# Power_supply.net
KiCad netlist of a schematic drawn in Altium Designer
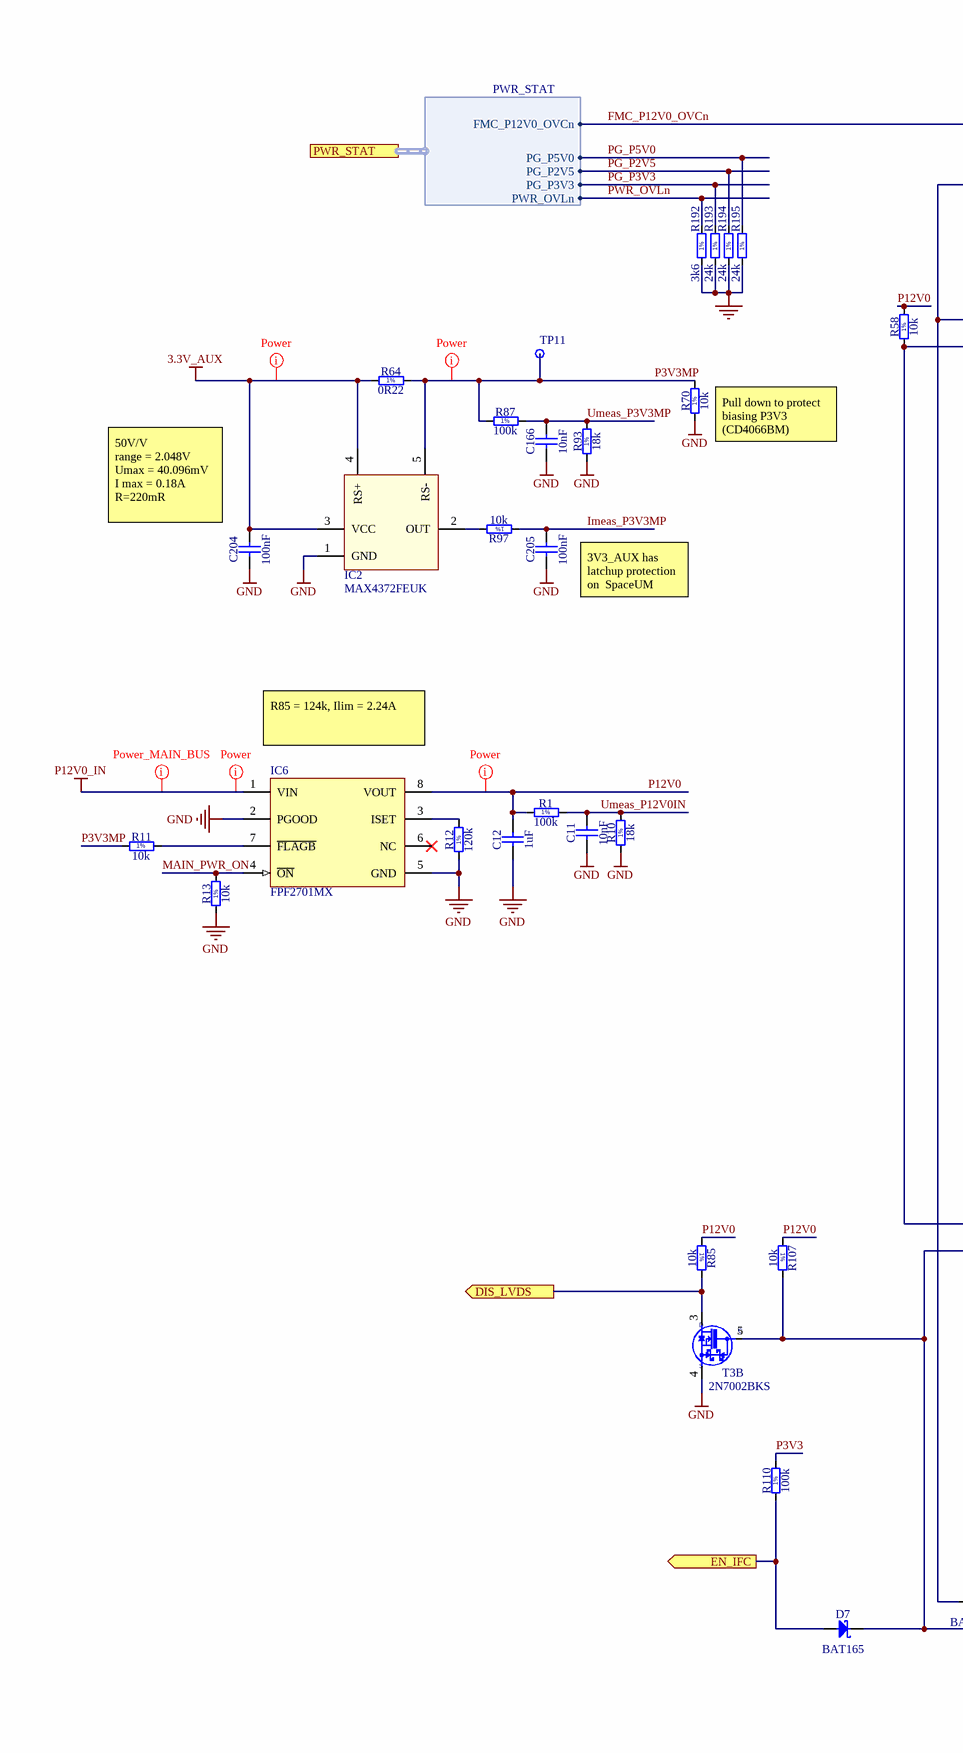
[diagram p0: Power_supply.SchDoc, left]
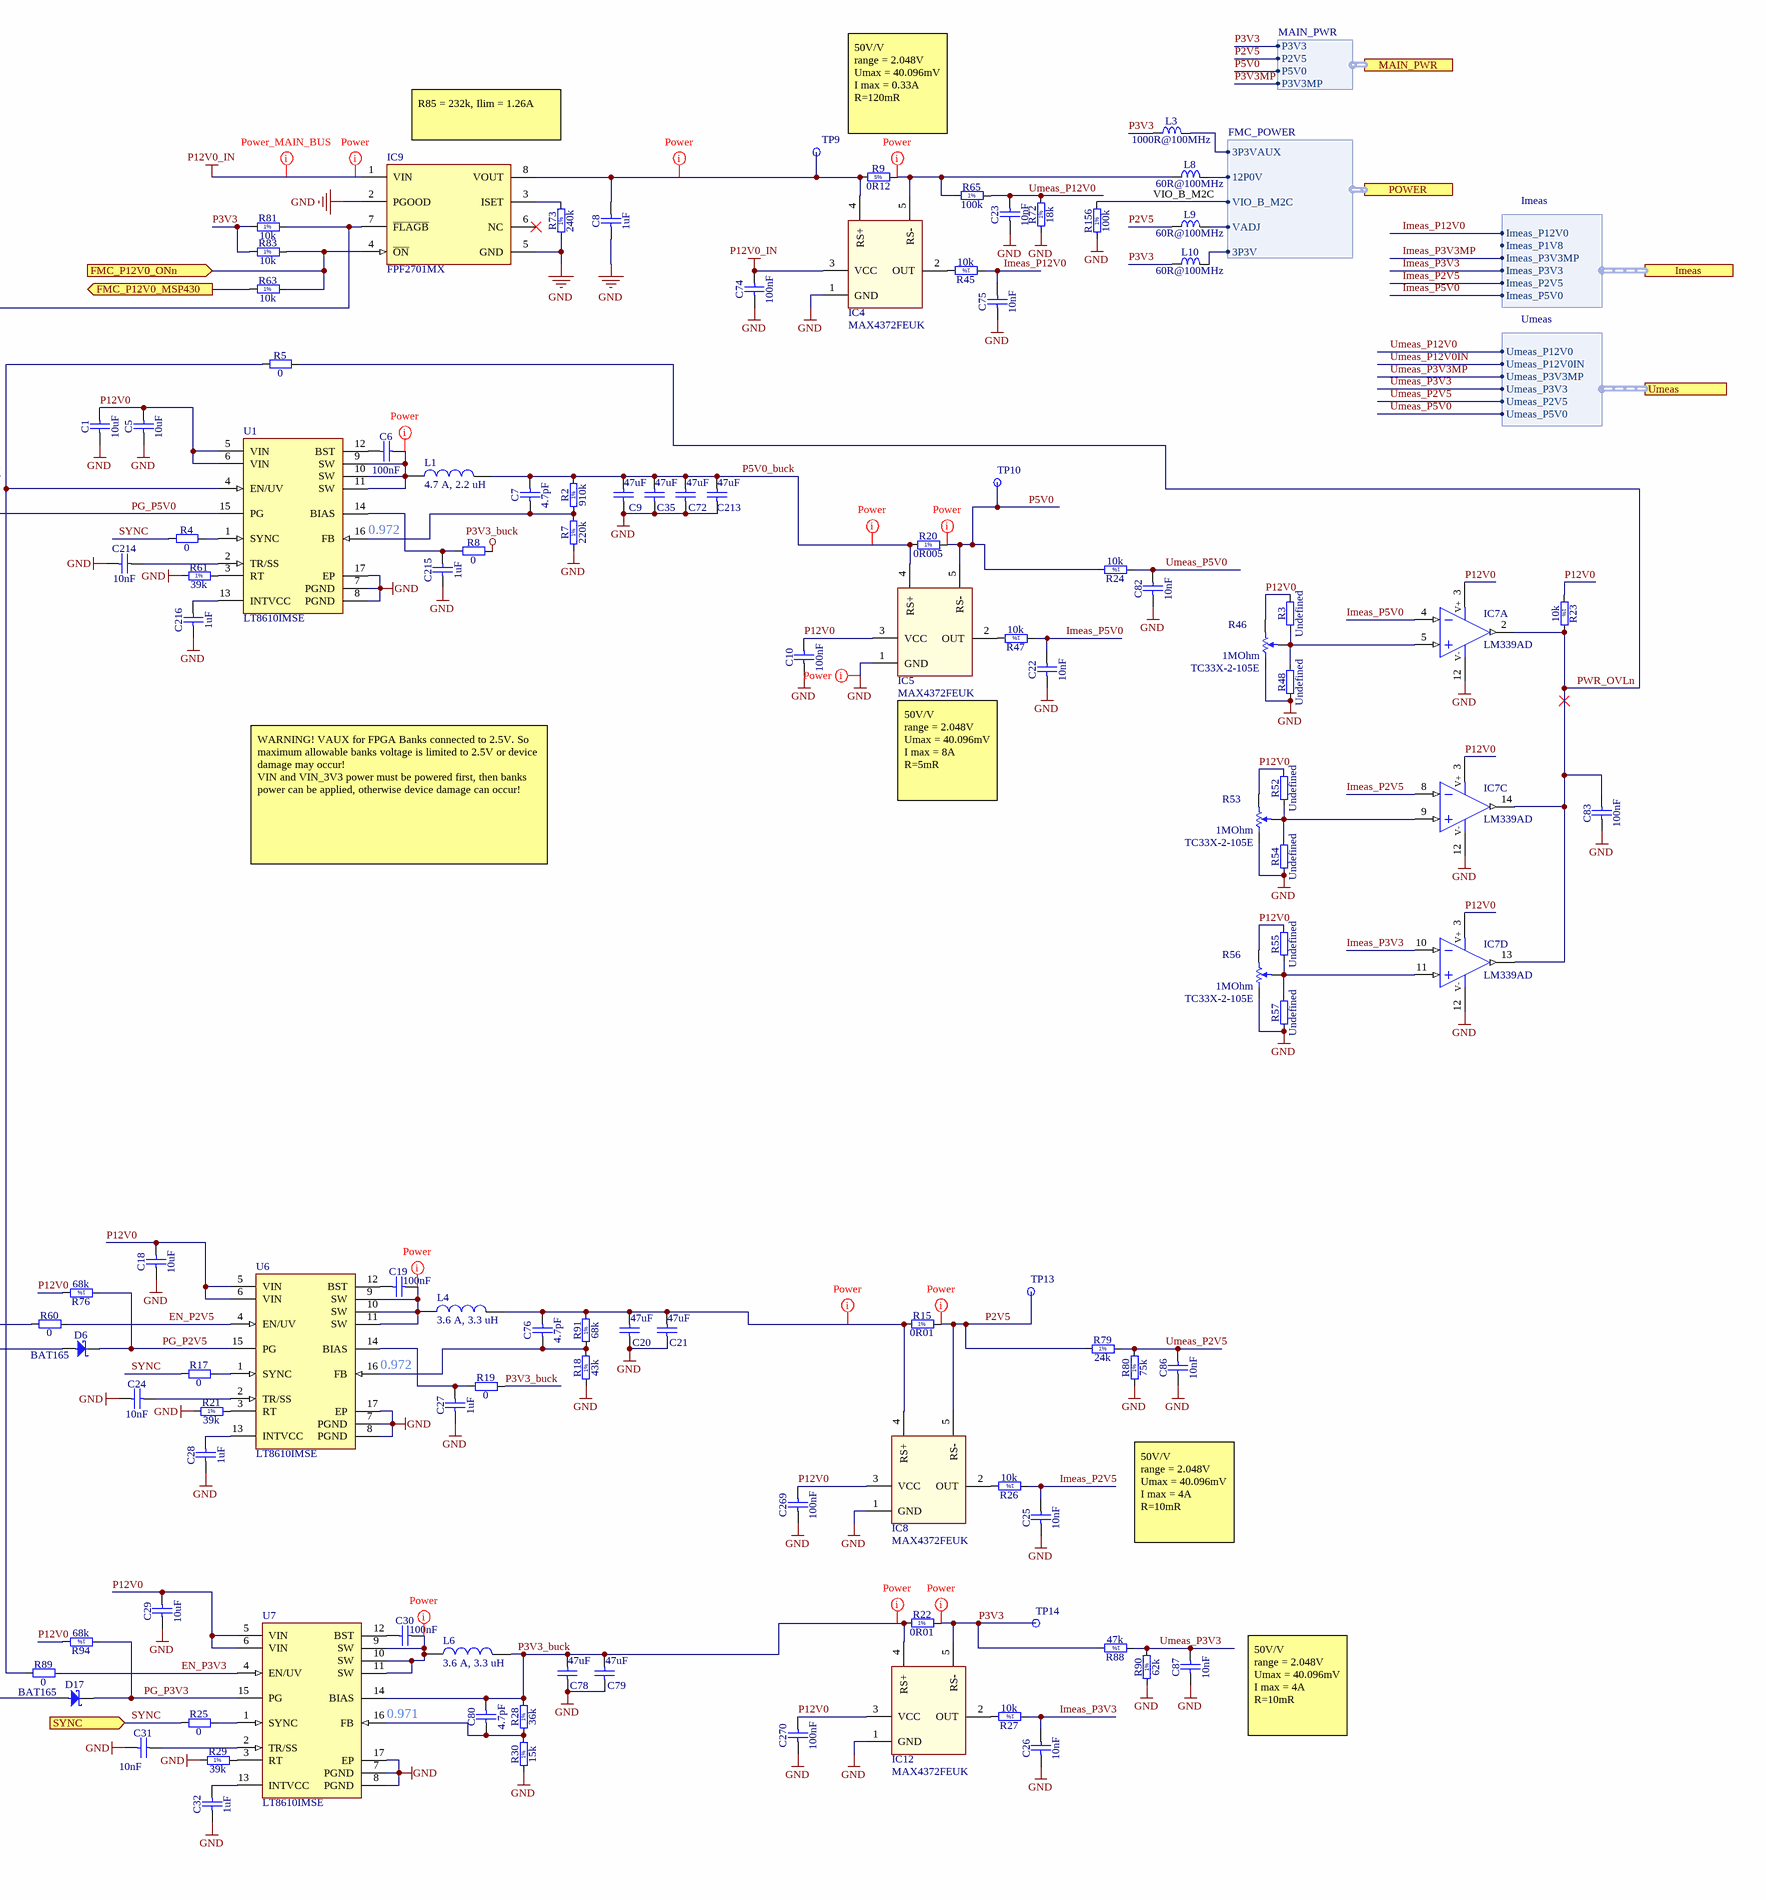
[diagram p1: Power_supply.SchDoc, right]

(export (version "E")
  (design (tool "Eeschema 10.0.6"))
  (components
    (comp (ref "C1")
      (value "10uF")
      (footprint "CAPC2012X95N")
      (description "Non-polarised capacitor")
      (fields
        (field (name "PART NUMBER") "CC0805_10UF_25V_10%_X5R")
        (field (name "VOLTAGE") "25V")
        (field (name "AUTHOR") "CERN DEM JLC")
      )
      (libsource (lib "Capacitors") (part "Capacitor - non polarized"))
    )
    (comp (ref "C5")
      (value "10uF")
      (footprint "CAPC2012X95N")
      (description "Non-polarised capacitor")
      (fields
        (field (name "PART NUMBER") "CC0805_10UF_25V_10%_X5R")
        (field (name "VOLTAGE") "25V")
        (field (name "AUTHOR") "CERN DEM JLC")
      )
      (libsource (lib "Capacitors") (part "Capacitor - non polarized"))
    )
    (comp (ref "C6")
      (value "100nF")
      (footprint "CAPC1005X55N")
      (description "Non-polarised capacitor")
      (fields
        (field (name "PART NUMBER") "CC0402_100NF_25V_10%_X7R_YUDEN_TMK105B7104KVHF")
        (field (name "VOLTAGE") "25V")
        (field (name "AUTHOR") "CERN DEM JLC")
      )
      (libsource (lib "Capacitors") (part "Capacitor - non polarized"))
    )
    (comp (ref "C7")
      (value "4.7pF")
      (footprint "CAPC1005X55N")
      (description "Non-polarised capacitor")
      (fields
        (field (name "PART NUMBER") "CC0402_4.7PF_50V_0.25PF_C0G")
        (field (name "VOLTAGE") "50V")
        (field (name "AUTHOR") "CERN DEM JLC")
      )
      (libsource (lib "Capacitors") (part "Capacitor - non polarized"))
    )
    (comp (ref "C8")
      (value "1uF")
      (footprint "CAPC1608X87N")
      (description "Non-polarised capacitor")
      (fields
        (field (name "PART NUMBER") "CC0603_1UF_25V_10%_X7R")
        (field (name "VOLTAGE") "25V")
        (field (name "AUTHOR") "CERN DEM JLC")
      )
      (libsource (lib "Capacitors") (part "Capacitor - non polarized"))
    )
    (comp (ref "C9")
      (value "47uF")
      (footprint "CAPC2012X140N")
      (description "Non-polarised capacitor")
      (fields
        (field (name "PART NUMBER") "CC0805_47UF_6.3V_20%_X5R")
        (field (name "MANUFACTURER") "GENERIC")
        (field (name "AUTHOR") "CERN DEM JLC")
      )
      (libsource (lib "Capacitors") (part "Capacitor - non polarized"))
    )
    (comp (ref "C10")
      (value "100nF")
      (footprint "CAPC1005X55N")
      (description "Non-polarised capacitor")
      (fields
        (field (name "PART NUMBER") "CC0402_100NF_25V_10%_X7R_YUDEN_TMK105B7104KVHF")
        (field (name "VOLTAGE") "25V")
        (field (name "AUTHOR") "CERN DEM JLC")
      )
      (libsource (lib "Capacitors") (part "Capacitor - non polarized"))
    )
    (comp (ref "C11")
      (value "10nF")
      (footprint "CAPC1005X55N")
      (description "Non-polarised capacitor")
      (fields
        (field (name "PART NUMBER") "CC0402_10NF_50V_10%_X7R")
        (field (name "VOLTAGE") "50V")
        (field (name "AUTHOR") "CERN DEM MR")
      )
      (libsource (lib "Capacitors") (part "Capacitor - non polarized"))
    )
    (comp (ref "C12")
      (value "1uF")
      (footprint "CAPC1608X87N")
      (description "Non-polarised capacitor")
      (fields
        (field (name "PART NUMBER") "CC0603_1UF_25V_10%_X7R")
        (field (name "VOLTAGE") "25V")
        (field (name "AUTHOR") "CERN DEM JLC")
      )
      (libsource (lib "Capacitors") (part "Capacitor - non polarized"))
    )
    (comp (ref "C18")
      (value "10uF")
      (footprint "CAPC2012X95N")
      (description "Non-polarised capacitor")
      (fields
        (field (name "PART NUMBER") "CC0805_10UF_25V_10%_X5R")
        (field (name "VOLTAGE") "25V")
        (field (name "AUTHOR") "CERN DEM JLC")
      )
      (libsource (lib "Capacitors") (part "Capacitor - non polarized"))
    )
    (comp (ref "C19")
      (value "100nF")
      (footprint "CAPC1005X55N")
      (description "Non-polarised capacitor")
      (fields
        (field (name "PART NUMBER") "CC0402_100NF_25V_10%_X7R_YUDEN_TMK105B7104KVHF")
        (field (name "VOLTAGE") "25V")
        (field (name "AUTHOR") "CERN DEM JLC")
      )
      (libsource (lib "Capacitors") (part "Capacitor - non polarized"))
    )
    (comp (ref "C20")
      (value "47uF")
      (footprint "CAPC2012X140N")
      (description "Non-polarised capacitor")
      (fields
        (field (name "PART NUMBER") "CC0805_47UF_6.3V_20%_X5R")
        (field (name "MANUFACTURER") "GENERIC")
        (field (name "AUTHOR") "CERN DEM JLC")
      )
      (libsource (lib "Capacitors") (part "Capacitor - non polarized"))
    )
    (comp (ref "C21")
      (value "47uF")
      (footprint "CAPC2012X140N")
      (description "Non-polarised capacitor")
      (fields
        (field (name "PART NUMBER") "CC0805_47UF_6.3V_20%_X5R")
        (field (name "MANUFACTURER") "GENERIC")
        (field (name "AUTHOR") "CERN DEM JLC")
      )
      (libsource (lib "Capacitors") (part "Capacitor - non polarized"))
    )
    (comp (ref "C22")
      (value "10nF")
      (footprint "CAPC1005X55N")
      (description "Non-polarised capacitor")
      (fields
        (field (name "PART NUMBER") "CC0402_10NF_50V_10%_X7R")
        (field (name "VOLTAGE") "50V")
        (field (name "AUTHOR") "CERN DEM MR")
      )
      (libsource (lib "Capacitors") (part "Capacitor - non polarized"))
    )
    (comp (ref "C23")
      (value "10nF")
      (footprint "CAPC1005X55N")
      (description "Non-polarised capacitor")
      (fields
        (field (name "PART NUMBER") "CC0402_10NF_50V_10%_X7R")
        (field (name "VOLTAGE") "50V")
        (field (name "AUTHOR") "CERN DEM MR")
      )
      (libsource (lib "Capacitors") (part "Capacitor - non polarized"))
    )
    (comp (ref "C24")
      (value "10nF")
      (footprint "CAPC1005X55N")
      (description "Non-polarised capacitor")
      (fields
        (field (name "PART NUMBER") "CC0402_10NF_25V_10%_X7R")
        (field (name "VOLTAGE") "25V")
        (field (name "AUTHOR") "CERN DEM JLC")
      )
      (libsource (lib "Capacitors") (part "Capacitor - non polarized"))
    )
    (comp (ref "C25")
      (value "10nF")
      (footprint "CAPC1005X55N")
      (description "Non-polarised capacitor")
      (fields
        (field (name "PART NUMBER") "CC0402_10NF_50V_10%_X7R")
        (field (name "VOLTAGE") "50V")
        (field (name "AUTHOR") "CERN DEM MR")
      )
      (libsource (lib "Capacitors") (part "Capacitor - non polarized"))
    )
    (comp (ref "C26")
      (value "10nF")
      (footprint "CAPC1005X55N")
      (description "Non-polarised capacitor")
      (fields
        (field (name "PART NUMBER") "CC0402_10NF_50V_10%_X7R")
        (field (name "VOLTAGE") "50V")
        (field (name "AUTHOR") "CERN DEM MR")
      )
      (libsource (lib "Capacitors") (part "Capacitor - non polarized"))
    )
    (comp (ref "C27")
      (value "1uF")
      (footprint "CAPC1608X87N")
      (description "Non-polarised capacitor")
      (fields
        (field (name "PART NUMBER") "CC0603_1UF_25V_10%_X7R")
        (field (name "VOLTAGE") "25V")
        (field (name "AUTHOR") "CERN DEM JLC")
      )
      (libsource (lib "Capacitors") (part "Capacitor - non polarized"))
    )
    (comp (ref "C28")
      (value "1uF")
      (footprint "CAPC1608X87N")
      (description "Non-polarised capacitor")
      (fields
        (field (name "PART NUMBER") "CC0603_1UF_25V_10%_X7R")
        (field (name "VOLTAGE") "25V")
        (field (name "AUTHOR") "CERN DEM JLC")
      )
      (libsource (lib "Capacitors") (part "Capacitor - non polarized"))
    )
    (comp (ref "C29")
      (value "10uF")
      (footprint "CAPC2012X95N")
      (description "Non-polarised capacitor")
      (fields
        (field (name "PART NUMBER") "CC0805_10UF_25V_10%_X5R")
        (field (name "VOLTAGE") "25V")
        (field (name "AUTHOR") "CERN DEM JLC")
      )
      (libsource (lib "Capacitors") (part "Capacitor - non polarized"))
    )
    (comp (ref "C30")
      (value "100nF")
      (footprint "CAPC1005X55N")
      (description "Non-polarised capacitor")
      (fields
        (field (name "PART NUMBER") "CC0402_100NF_25V_10%_X7R_YUDEN_TMK105B7104KVHF")
        (field (name "VOLTAGE") "25V")
        (field (name "AUTHOR") "CERN DEM JLC")
      )
      (libsource (lib "Capacitors") (part "Capacitor - non polarized"))
    )
    (comp (ref "C31")
      (value "10nF")
      (footprint "CAPC1005X55N")
      (description "Non-polarised capacitor")
      (fields
        (field (name "PART NUMBER") "CC0402_10NF_25V_10%_X7R")
        (field (name "VOLTAGE") "25V")
        (field (name "AUTHOR") "CERN DEM JLC")
      )
      (libsource (lib "Capacitors") (part "Capacitor - non polarized"))
    )
    (comp (ref "C32")
      (value "1uF")
      (footprint "CAPC1608X87N")
      (description "Non-polarised capacitor")
      (fields
        (field (name "PART NUMBER") "CC0603_1UF_25V_10%_X7R")
        (field (name "VOLTAGE") "25V")
        (field (name "AUTHOR") "CERN DEM JLC")
      )
      (libsource (lib "Capacitors") (part "Capacitor - non polarized"))
    )
    (comp (ref "C35")
      (value "47uF")
      (footprint "CAPC2012X140N")
      (description "Non-polarised capacitor")
      (fields
        (field (name "PART NUMBER") "CC0805_47UF_6.3V_20%_X5R")
        (field (name "MANUFACTURER") "GENERIC")
        (field (name "AUTHOR") "CERN DEM JLC")
      )
      (libsource (lib "Capacitors") (part "Capacitor - non polarized"))
    )
    (comp (ref "C72")
      (value "47uF")
      (footprint "CAPC2012X140N")
      (description "Non-polarised capacitor")
      (fields
        (field (name "PART NUMBER") "CC0805_47UF_6.3V_20%_X5R")
        (field (name "MANUFACTURER") "GENERIC")
        (field (name "AUTHOR") "CERN DEM JLC")
      )
      (libsource (lib "Capacitors") (part "Capacitor - non polarized"))
    )
    (comp (ref "C74")
      (value "100nF")
      (footprint "CAPC1005X55N")
      (description "Non-polarised capacitor")
      (fields
        (field (name "PART NUMBER") "CC0402_100NF_25V_10%_X7R_YUDEN_TMK105B7104KVHF")
        (field (name "VOLTAGE") "25V")
        (field (name "AUTHOR") "CERN DEM JLC")
      )
      (libsource (lib "Capacitors") (part "Capacitor - non polarized"))
    )
    (comp (ref "C75")
      (value "10nF")
      (footprint "CAPC1005X55N")
      (description "Non-polarised capacitor")
      (fields
        (field (name "PART NUMBER") "CC0402_10NF_50V_10%_X7R")
        (field (name "VOLTAGE") "50V")
        (field (name "AUTHOR") "CERN DEM MR")
      )
      (libsource (lib "Capacitors") (part "Capacitor - non polarized"))
    )
    (comp (ref "C76")
      (value "4.7pF")
      (footprint "CAPC1005X55N")
      (description "Non-polarised capacitor")
      (fields
        (field (name "PART NUMBER") "CC0402_4.7PF_50V_0.25PF_C0G")
        (field (name "VOLTAGE") "50V")
        (field (name "AUTHOR") "CERN DEM JLC")
      )
      (libsource (lib "Capacitors") (part "Capacitor - non polarized"))
    )
    (comp (ref "C78")
      (value "47uF")
      (footprint "CAPC2012X140N")
      (description "Non-polarised capacitor")
      (fields
        (field (name "PART NUMBER") "CC0805_47UF_6.3V_20%_X5R")
        (field (name "MANUFACTURER") "GENERIC")
        (field (name "AUTHOR") "CERN DEM JLC")
      )
      (libsource (lib "Capacitors") (part "Capacitor - non polarized"))
    )
    (comp (ref "C79")
      (value "47uF")
      (footprint "CAPC2012X140N")
      (description "Non-polarised capacitor")
      (fields
        (field (name "PART NUMBER") "CC0805_47UF_6.3V_20%_X5R")
        (field (name "MANUFACTURER") "GENERIC")
        (field (name "AUTHOR") "CERN DEM JLC")
      )
      (libsource (lib "Capacitors") (part "Capacitor - non polarized"))
    )
    (comp (ref "C80")
      (value "4.7pF")
      (footprint "CAPC1005X55N")
      (description "Non-polarised capacitor")
      (fields
        (field (name "PART NUMBER") "CC0402_4.7PF_50V_0.25PF_C0G")
        (field (name "VOLTAGE") "50V")
        (field (name "AUTHOR") "CERN DEM JLC")
      )
      (libsource (lib "Capacitors") (part "Capacitor - non polarized"))
    )
    (comp (ref "C82")
      (value "10nF")
      (footprint "CAPC1005X55N")
      (description "Non-polarised capacitor")
      (fields
        (field (name "PART NUMBER") "CC0402_10NF_50V_10%_X7R")
        (field (name "VOLTAGE") "50V")
        (field (name "AUTHOR") "CERN DEM MR")
      )
      (libsource (lib "Capacitors") (part "Capacitor - non polarized"))
    )
    (comp (ref "C83")
      (value "100nF")
      (footprint "CAPC1005X55N")
      (description "Non-polarised capacitor")
      (fields
        (field (name "PART NUMBER") "CC0402_100NF_25V_10%_X7R_YUDEN_TMK105B7104KVHF")
        (field (name "VOLTAGE") "25V")
        (field (name "AUTHOR") "CERN DEM JLC")
      )
      (libsource (lib "Capacitors") (part "Capacitor - non polarized"))
    )
    (comp (ref "C86")
      (value "10nF")
      (footprint "CAPC1005X55N")
      (description "Non-polarised capacitor")
      (fields
        (field (name "PART NUMBER") "CC0402_10NF_50V_10%_X7R")
        (field (name "VOLTAGE") "50V")
        (field (name "AUTHOR") "CERN DEM MR")
      )
      (libsource (lib "Capacitors") (part "Capacitor - non polarized"))
    )
    (comp (ref "C87")
      (value "10nF")
      (footprint "CAPC1005X55N")
      (description "Non-polarised capacitor")
      (fields
        (field (name "PART NUMBER") "CC0402_10NF_50V_10%_X7R")
        (field (name "VOLTAGE") "50V")
        (field (name "AUTHOR") "CERN DEM MR")
      )
      (libsource (lib "Capacitors") (part "Capacitor - non polarized"))
    )
    (comp (ref "C166")
      (value "10nF")
      (footprint "CAPC1005X55N")
      (description "Non-polarised capacitor")
      (fields
        (field (name "PART NUMBER") "CC0402_10NF_50V_10%_X7R")
        (field (name "VOLTAGE") "50V")
        (field (name "AUTHOR") "CERN DEM MR")
      )
      (libsource (lib "Capacitors") (part "Capacitor - non polarized"))
    )
    (comp (ref "C204")
      (value "100nF")
      (footprint "CAPC1005X55N")
      (description "Non-polarised capacitor")
      (fields
        (field (name "PART NUMBER") "CC0402_100NF_25V_10%_X7R_YUDEN_TMK105B7104KVHF")
        (field (name "VOLTAGE") "25V")
        (field (name "AUTHOR") "CERN DEM JLC")
      )
      (libsource (lib "Capacitors") (part "Capacitor - non polarized"))
    )
    (comp (ref "C205")
      (value "100nF")
      (footprint "CAPC1005X55N")
      (description "Non-polarised capacitor")
      (fields
        (field (name "PART NUMBER") "CC0402_100NF_25V_10%_X7R_YUDEN_TMK105B7104KVHF")
        (field (name "VOLTAGE") "25V")
        (field (name "AUTHOR") "CERN DEM JLC")
      )
      (libsource (lib "Capacitors") (part "Capacitor - non polarized"))
    )
    (comp (ref "C213")
      (value "47uF")
      (footprint "CAPC2012X140N")
      (description "Non-polarised capacitor")
      (fields
        (field (name "PART NUMBER") "CC0805_47UF_6.3V_20%_X5R")
        (field (name "MANUFACTURER") "GENERIC")
        (field (name "AUTHOR") "CERN DEM JLC")
      )
      (libsource (lib "Capacitors") (part "Capacitor - non polarized"))
    )
    (comp (ref "C214")
      (value "10nF")
      (footprint "CAPC1005X55N")
      (description "Non-polarised capacitor")
      (fields
        (field (name "PART NUMBER") "CC0402_10NF_25V_10%_X7R")
        (field (name "VOLTAGE") "25V")
        (field (name "AUTHOR") "CERN DEM JLC")
      )
      (libsource (lib "Capacitors") (part "Capacitor - non polarized"))
    )
    (comp (ref "C215")
      (value "1uF")
      (footprint "CAPC1608X87N")
      (description "Non-polarised capacitor")
      (fields
        (field (name "PART NUMBER") "CC0603_1UF_25V_10%_X7R")
        (field (name "VOLTAGE") "25V")
        (field (name "AUTHOR") "CERN DEM JLC")
      )
      (libsource (lib "Capacitors") (part "Capacitor - non polarized"))
    )
    (comp (ref "C216")
      (value "1uF")
      (footprint "CAPC1608X87N")
      (description "Non-polarised capacitor")
      (fields
        (field (name "PART NUMBER") "CC0603_1UF_25V_10%_X7R")
        (field (name "VOLTAGE") "25V")
        (field (name "AUTHOR") "CERN DEM JLC")
      )
      (libsource (lib "Capacitors") (part "Capacitor - non polarized"))
    )
    (comp (ref "C269")
      (value "100nF")
      (footprint "CAPC1005X55N")
      (description "Non-polarised capacitor")
      (fields
        (field (name "PART NUMBER") "CC0402_100NF_25V_10%_X7R_YUDEN_TMK105B7104KVHF")
        (field (name "VOLTAGE") "25V")
        (field (name "AUTHOR") "CERN DEM JLC")
      )
      (libsource (lib "Capacitors") (part "Capacitor - non polarized"))
    )
    (comp (ref "C270")
      (value "100nF")
      (footprint "CAPC1005X55N")
      (description "Non-polarised capacitor")
      (fields
        (field (name "PART NUMBER") "CC0402_100NF_25V_10%_X7R_YUDEN_TMK105B7104KVHF")
        (field (name "VOLTAGE") "25V")
        (field (name "AUTHOR") "CERN DEM JLC")
      )
      (libsource (lib "Capacitors") (part "Capacitor - non polarized"))
    )
    (comp (ref "D6")
      (value "BAT165")
      (footprint "SOD2512X110N")
      (description "Schottky Diode")
      (fields
        (field (name "VOLTAGE") "40V")
        (field (name "POWER") "750mA")
        (field (name "AUTHOR") "CERN DEM JLC")
      )
      (libsource (lib "ICs And Semiconductors") (part "Diode Schottky"))
    )
    (comp (ref "D7")
      (value "BAT165")
      (footprint "SOD2512X110N")
      (description "Schottky Diode")
      (fields
        (field (name "VOLTAGE") "40V")
        (field (name "POWER") "750mA")
        (field (name "AUTHOR") "CERN DEM JLC")
      )
      (libsource (lib "ICs And Semiconductors") (part "Diode Schottky"))
    )
    (comp (ref "D17")
      (value "BAT165")
      (footprint "SOD2512X110N")
      (description "Schottky Diode")
      (fields
        (field (name "VOLTAGE") "40V")
        (field (name "POWER") "750mA")
        (field (name "AUTHOR") "CERN DEM JLC")
      )
      (libsource (lib "ICs And Semiconductors") (part "Diode Schottky"))
    )
    (comp (ref "IC2")
      (value "MAX4372FEUK")
      (footprint "SOT95P270X145-5N")
      (description "High side current sense amplifier (x50)")
      (fields (field (name "MANUFACTURER") "Maxim"))
      (libsource (lib "ICs_And_Semiconductors") (part "MAX4372FEUK"))
    )
    (comp (ref "IC4")
      (value "MAX4372FEUK")
      (footprint "SOT95P270X145-5N")
      (fields (field (name "MANUFACTURER") "Maxim"))
      (libsource (lib "LIBRARY_SCH") (part "PM_MAX4372FEUK"))
    )
    (comp (ref "IC5")
      (value "MAX4372FEUK")
      (footprint "SOT95P270X145-5N")
      (fields (field (name "MANUFACTURER") "Maxim"))
      (libsource (lib "LIBRARY_SCH") (part "PM_MAX4372FEUK"))
    )
    (comp (ref "IC6")
      (value "FPF2701MX")
      (footprint "SOIC127P600X175-8N")
      (description "Adjustable Over-current Protection Load Switch")
      (fields (field (name "MANUFACTURER") "ON Semiconductor"))
      (libsource (lib "ICs_And_Semiconductors") (part "FPF2701MX"))
    )
    (comp (ref "IC7")
      (value "LM339AD")
      (footprint "SOIC127P600X175-14N")
      (description "Quad Operational Amplifier")
      (fields (field (name "MANUFACTURER") "TEXAS INSTRUMENTS") (field (name "AUTHOR") "CERN DEM JLC"))
      (libsource (lib "ICs And Semiconductors") (part "Operational Amplifier x4 Type2"))
    )
    (comp (ref "IC8")
      (value "MAX4372FEUK")
      (footprint "SOT95P270X145-5N")
      (fields (field (name "MANUFACTURER") "Maxim"))
      (libsource (lib "LIBRARY_SCH") (part "PM_MAX4372FEUK"))
    )
    (comp (ref "IC9")
      (value "FPF2701MX")
      (footprint "SOIC127P600X175-8N")
      (description "Adjustable Over-current Protection Load Switch")
      (fields (field (name "MANUFACTURER") "ON Semiconductor"))
      (libsource (lib "ICs_And_Semiconductors") (part "FPF2701MX"))
    )
    (comp (ref "IC12")
      (value "MAX4372FEUK")
      (footprint "SOT95P270X145-5N")
      (fields (field (name "MANUFACTURER") "Maxim"))
      (libsource (lib "LIBRARY_SCH") (part "PM_MAX4372FEUK"))
    )
    (comp (ref "L1")
      (value "4.7 A, 2.2 uH")
      (footprint "WE-MAIA_4020")
      (description "WE-MAIA SMD Power Inductor, size 4020, 4.7 A, 2.2 uH")
      (fields (field (name "PART NUMBER") "78438356022") (field (name "PUBLISHER") "Wurth Elektronik"))
      (libsource (lib "ALTIUM-WE-MAIA-rev17b") (part "78438356022"))
    )
    (comp (ref "L3")
      (value "1000R@100MHz")
      (footprint "INDC1608X95N")
      (description "Inductor")
      (fields
        (field (name "PART NUMBER") "IND0603_MURATA_BLM18HE102SN1")
        (field (name "POWER") "600mA")
        (field (name "AUTHOR") "CERN DEM JLC")
      )
      (libsource (lib "Inductors & Transformers") (part "Inductor"))
    )
    (comp (ref "L4")
      (value "3.6 A, 3.3 uH")
      (footprint "WE-MAIA_4020")
      (description "WE-MAIA SMD Power Inductor, size 4020, 3.6 A, 3.3 uH")
      (fields (field (name "PART NUMBER") "78438356033") (field (name "PUBLISHER") "Wurth Elektronik"))
      (libsource (lib "ALTIUM-WE-MAIA-rev17b") (part "78438356033"))
    )
    (comp (ref "L6")
      (value "3.6 A, 3.3 uH")
      (footprint "WE-MAIA_4020")
      (description "WE-MAIA SMD Power Inductor, size 4020, 3.6 A, 3.3 uH")
      (fields (field (name "PART NUMBER") "78438356033") (field (name "PUBLISHER") "Wurth Elektronik"))
      (libsource (lib "ALTIUM-WE-MAIA-rev17b") (part "78438356033"))
    )
    (comp (ref "L8")
      (value "60R@100MHz")
      (footprint "INDC4516X180N")
      (description "Inductor")
      (fields
        (field (name "PART NUMBER") "IND1806_MURATA_BLM41PG600SN1L")
        (field (name "POWER") "6A")
        (field (name "AUTHOR") "CERN DEM JLC")
      )
      (libsource (lib "Inductors & Transformers") (part "Inductor"))
    )
    (comp (ref "L9")
      (value "60R@100MHz")
      (footprint "INDC4516X180N")
      (description "Inductor")
      (fields
        (field (name "PART NUMBER") "IND1806_MURATA_BLM41PG600SN1L")
        (field (name "POWER") "6A")
        (field (name "AUTHOR") "CERN DEM JLC")
      )
      (libsource (lib "Inductors & Transformers") (part "Inductor"))
    )
    (comp (ref "L10")
      (value "60R@100MHz")
      (footprint "INDC4516X180N")
      (description "Inductor")
      (fields
        (field (name "PART NUMBER") "IND1806_MURATA_BLM41PG600SN1L")
        (field (name "POWER") "6A")
        (field (name "AUTHOR") "CERN DEM JLC")
      )
      (libsource (lib "Inductors & Transformers") (part "Inductor"))
    )
    (comp (ref "R1")
      (value "100k")
      (footprint "RESC1005X40N")
      (description "Resistor - 1%")
      (fields
        (field (name "PART NUMBER") "R0402_100K_1%_0.0625W_100PPM")
        (field (name "POWER") "0.0625W")
        (field (name "AUTHOR") "CERN DEM JLC")
      )
      (libsource (lib "Resistors") (part "Resistor - 1%"))
    )
    (comp (ref "R2")
      (value "910k")
      (footprint "RESC1005X40N")
      (description "Resistor - 1%")
      (fields
        (field (name "PART NUMBER") "R0402_910K_1%_0.0625W_100PPM")
        (field (name "POWER") "0.0625W")
        (field (name "AUTHOR") "CERN DEM JLC")
      )
      (libsource (lib "Resistors") (part "Resistor - 1%"))
    )
    (comp (ref "R3")
      (value "Undefined")
      (footprint "RESC1005X40N")
      (description "Resistor")
      (fields (field (name "PART NUMBER") "R0402_NO-VALUE") (field (name "AUTHOR") "CERN DEM JLC"))
      (libsource (lib "Resistors") (part "Resistor"))
    )
    (comp (ref "R4")
      (value "0")
      (footprint "RESC1005X40N")
      (description "Resistor")
      (fields
        (field (name "PART NUMBER") "R0402_0R_JUMPER")
        (field (name "MANUFACTURER") "GENERIC")
        (field (name "AUTHOR") "CERN DEM JLC")
      )
      (libsource (lib "Resistors") (part "Resistor"))
    )
    (comp (ref "R5")
      (value "0")
      (footprint "RESC1005X40N")
      (description "Resistor")
      (fields
        (field (name "PART NUMBER") "R0402_0R_JUMPER")
        (field (name "MANUFACTURER") "GENERIC")
        (field (name "AUTHOR") "CERN DEM JLC")
      )
      (libsource (lib "Resistors") (part "Resistor"))
    )
    (comp (ref "R7")
      (value "220k")
      (footprint "RESC1005X40N")
      (description "Resistor - 1%")
      (fields
        (field (name "PART NUMBER") "R0402_220K_1%_0.0625W_100PPM")
        (field (name "POWER") "0.0625W")
        (field (name "AUTHOR") "CERN DEM JLC")
      )
      (libsource (lib "Resistors") (part "Resistor - 1%"))
    )
    (comp (ref "R8")
      (value "0")
      (footprint "RESC1005X40N")
      (description "Resistor")
      (fields
        (field (name "PART NUMBER") "R0402_0R_JUMPER")
        (field (name "MANUFACTURER") "GENERIC")
        (field (name "AUTHOR") "CERN DEM JLC")
      )
      (libsource (lib "Resistors") (part "Resistor"))
    )
    (comp (ref "R9")
      (value "0R12")
      (footprint "RESC2012X70N")
      (description "Resistor - 5%")
      (fields
        (field (name "PART NUMBER") "R0805_0R12_5%_0.25W_250PPM_PANASONIC_ERJ")
        (field (name "POWER") "0.25W")
        (field (name "AUTHOR") "CERN DEM JLC")
      )
      (libsource (lib "Resistors") (part "Resistor - 5%"))
    )
    (comp (ref "R10")
      (value "18k")
      (footprint "RESC1005X40N")
      (description "Resistor - 1%")
      (fields
        (field (name "PART NUMBER") "R0402_18K_1%_0.0625W_100PPM")
        (field (name "POWER") "0.0625W")
        (field (name "AUTHOR") "CERN DEM JLC")
      )
      (libsource (lib "Resistors") (part "Resistor - 1%"))
    )
    (comp (ref "R11")
      (value "10k")
      (footprint "RESC1005X40N")
      (description "Resistor - 1%")
      (fields
        (field (name "PART NUMBER") "R0402_10K_1%_0.0625W_100PPM")
        (field (name "POWER") "0.0625W")
        (field (name "AUTHOR") "CERN DEM JLC")
      )
      (libsource (lib "Resistors") (part "Resistor - 1%"))
    )
    (comp (ref "R12")
      (value "120k")
      (footprint "RESC1005X40N")
      (description "Resistor - 1%")
      (fields
        (field (name "PART NUMBER") "R0402_120K_1%_0.0625W_100PPM")
        (field (name "POWER") "0.0625W")
        (field (name "AUTHOR") "CERN DEM JLC")
      )
      (libsource (lib "Resistors") (part "Resistor - 1%"))
    )
    (comp (ref "R13")
      (value "10k")
      (footprint "RESC1005X40N")
      (description "Resistor - 1%")
      (fields
        (field (name "PART NUMBER") "R0402_10K_1%_0.0625W_100PPM")
        (field (name "POWER") "0.0625W")
        (field (name "AUTHOR") "CERN DEM JLC")
      )
      (libsource (lib "Resistors") (part "Resistor - 1%"))
    )
    (comp (ref "R15")
      (value "0R01")
      (footprint "RESC3216X80N")
      (description "Resistor - 1%")
      (fields
        (field (name "PART NUMBER") "R1206_0R01_1%_1W_100PPM_TT_LRMAM1206")
        (field (name "POWER") "1W")
        (field (name "AUTHOR") "CERN DEM BC")
      )
      (libsource (lib "Resistors") (part "Resistor - 1%"))
    )
    (comp (ref "R17")
      (value "0")
      (footprint "RESC1005X40N")
      (description "Resistor")
      (fields
        (field (name "PART NUMBER") "R0402_0R_JUMPER")
        (field (name "MANUFACTURER") "GENERIC")
        (field (name "AUTHOR") "CERN DEM JLC")
      )
      (libsource (lib "Resistors") (part "Resistor"))
    )
    (comp (ref "R18")
      (value "43k")
      (footprint "RESC1005X40N")
      (description "Resistor - 1%")
      (fields
        (field (name "PART NUMBER") "R0402_43K_1%_0.0625W_100PPM")
        (field (name "POWER") "0.0625W")
        (field (name "AUTHOR") "CERN DEM JLC")
      )
      (libsource (lib "Resistors") (part "Resistor - 1%"))
    )
    (comp (ref "R19")
      (value "0")
      (footprint "RESC1005X40N")
      (description "Resistor")
      (fields
        (field (name "PART NUMBER") "R0402_0R_JUMPER")
        (field (name "MANUFACTURER") "GENERIC")
        (field (name "AUTHOR") "CERN DEM JLC")
      )
      (libsource (lib "Resistors") (part "Resistor"))
    )
    (comp (ref "R20")
      (value "0R005")
      (footprint "RESC3216X80N")
      (description "Resistor - 1%")
      (fields
        (field (name "PART NUMBER") "R1206_0R005_1%_1W_100PPM_TT_LRMAM1206")
        (field (name "POWER") "1W")
        (field (name "AUTHOR") "CERN DEM BC")
      )
      (libsource (lib "Resistors") (part "Resistor - 1%"))
    )
    (comp (ref "R21")
      (value "39k")
      (footprint "RESC1005X40N")
      (description "Resistor - 1%")
      (fields
        (field (name "PART NUMBER") "R0402_39K_1%_0.0625W_100PPM")
        (field (name "POWER") "0.0625W")
        (field (name "AUTHOR") "CERN DEM JLC")
      )
      (libsource (lib "Resistors") (part "Resistor - 1%"))
    )
    (comp (ref "R22")
      (value "0R01")
      (footprint "RESC3216X80N")
      (description "Resistor - 1%")
      (fields
        (field (name "PART NUMBER") "R1206_0R01_1%_1W_100PPM_TT_LRMAM1206")
        (field (name "POWER") "1W")
        (field (name "AUTHOR") "CERN DEM BC")
      )
      (libsource (lib "Resistors") (part "Resistor - 1%"))
    )
    (comp (ref "R23")
      (value "10k")
      (footprint "RESC1005X40N")
      (description "Resistor - 1%")
      (fields
        (field (name "PART NUMBER") "R0402_10K_1%_0.0625W_100PPM")
        (field (name "POWER") "0.0625W")
        (field (name "AUTHOR") "CERN DEM JLC")
      )
      (libsource (lib "Resistors") (part "Resistor - 1%"))
    )
    (comp (ref "R24")
      (value "10k")
      (footprint "RESC1005X40N")
      (description "Resistor - 1%")
      (fields
        (field (name "PART NUMBER") "R0402_10K_1%_0.0625W_100PPM")
        (field (name "POWER") "0.0625W")
        (field (name "AUTHOR") "CERN DEM JLC")
      )
      (libsource (lib "Resistors") (part "Resistor - 1%"))
    )
    (comp (ref "R25")
      (value "0")
      (footprint "RESC1005X40N")
      (description "Resistor")
      (fields
        (field (name "PART NUMBER") "R0402_0R_JUMPER")
        (field (name "MANUFACTURER") "GENERIC")
        (field (name "AUTHOR") "CERN DEM JLC")
      )
      (libsource (lib "Resistors") (part "Resistor"))
    )
    (comp (ref "R26")
      (value "10k")
      (footprint "RESC1005X40N")
      (description "Resistor - 1%")
      (fields
        (field (name "PART NUMBER") "R0402_10K_1%_0.0625W_100PPM")
        (field (name "POWER") "0.0625W")
        (field (name "AUTHOR") "CERN DEM JLC")
      )
      (libsource (lib "Resistors") (part "Resistor - 1%"))
    )
    (comp (ref "R27")
      (value "10k")
      (footprint "RESC1005X40N")
      (description "Resistor - 1%")
      (fields
        (field (name "PART NUMBER") "R0402_10K_1%_0.0625W_100PPM")
        (field (name "POWER") "0.0625W")
        (field (name "AUTHOR") "CERN DEM JLC")
      )
      (libsource (lib "Resistors") (part "Resistor - 1%"))
    )
    (comp (ref "R28")
      (value "36k")
      (footprint "RESC1005X40N")
      (description "Resistor - 1%")
      (fields
        (field (name "PART NUMBER") "R0402_36K_1%_0.0625W_100PPM")
        (field (name "POWER") "0.0625W")
        (field (name "AUTHOR") "CERN DEM JLC")
      )
      (libsource (lib "Resistors") (part "Resistor - 1%"))
    )
    (comp (ref "R29")
      (value "39k")
      (footprint "RESC1005X40N")
      (description "Resistor - 1%")
      (fields
        (field (name "PART NUMBER") "R0402_39K_1%_0.0625W_100PPM")
        (field (name "POWER") "0.0625W")
        (field (name "AUTHOR") "CERN DEM JLC")
      )
      (libsource (lib "Resistors") (part "Resistor - 1%"))
    )
    (comp (ref "R30")
      (value "15k")
      (footprint "RESC1005X40N")
      (description "Resistor - 1%")
      (fields
        (field (name "PART NUMBER") "R0402_15K_1%_0.0625W_100PPM")
        (field (name "POWER") "0.0625W")
        (field (name "AUTHOR") "CERN DEM JMW")
      )
      (libsource (lib "Resistors") (part "Resistor - 1%"))
    )
    (comp (ref "R45")
      (value "10k")
      (footprint "RESC1005X40N")
      (description "Resistor - 1%")
      (fields
        (field (name "PART NUMBER") "R0402_10K_1%_0.0625W_100PPM")
        (field (name "POWER") "0.0625W")
        (field (name "AUTHOR") "CERN DEM JLC")
      )
      (libsource (lib "Resistors") (part "Resistor - 1%"))
    )
    (comp (ref "R46")
      (value "TC33X-2-105E")
      (footprint "BOUR-TC33X-2_V")
      (description "Trimming Potentiometer, 1M Ohm, -40 to 100 degC, 3-Pin SMD, RoHS, Tape and Reel")
      (fields
        (field (name "TOLERANCE") "25%")
        (field (name "RESISTANCE") "1MOhm")
        (field (name "MANUFACTURER") "Bourns")
      )
      (libsource (lib "LIBRARY_SCH") (part "TRIMPOT_TC33X_1M"))
    )
    (comp (ref "R47")
      (value "10k")
      (footprint "RESC1005X40N")
      (description "Resistor - 1%")
      (fields
        (field (name "PART NUMBER") "R0402_10K_1%_0.0625W_100PPM")
        (field (name "POWER") "0.0625W")
        (field (name "AUTHOR") "CERN DEM JLC")
      )
      (libsource (lib "Resistors") (part "Resistor - 1%"))
    )
    (comp (ref "R48")
      (value "Undefined")
      (footprint "RESC1005X40N")
      (description "Resistor")
      (fields (field (name "PART NUMBER") "R0402_NO-VALUE") (field (name "AUTHOR") "CERN DEM JLC"))
      (libsource (lib "Resistors") (part "Resistor"))
    )
    (comp (ref "R52")
      (value "Undefined")
      (footprint "RESC1005X40N")
      (description "Resistor")
      (fields (field (name "PART NUMBER") "R0402_NO-VALUE") (field (name "AUTHOR") "CERN DEM JLC"))
      (libsource (lib "Resistors") (part "Resistor"))
    )
    (comp (ref "R53")
      (value "TC33X-2-105E")
      (footprint "BOUR-TC33X-2_V")
      (description "Trimming Potentiometer, 1M Ohm, -40 to 100 degC, 3-Pin SMD, RoHS, Tape and Reel")
      (fields
        (field (name "TOLERANCE") "25%")
        (field (name "RESISTANCE") "1MOhm")
        (field (name "MANUFACTURER") "Bourns")
      )
      (libsource (lib "LIBRARY_SCH") (part "TRIMPOT_TC33X_1M"))
    )
    (comp (ref "R54")
      (value "Undefined")
      (footprint "RESC1005X40N")
      (description "Resistor")
      (fields (field (name "PART NUMBER") "R0402_NO-VALUE") (field (name "AUTHOR") "CERN DEM JLC"))
      (libsource (lib "Resistors") (part "Resistor"))
    )
    (comp (ref "R55")
      (value "Undefined")
      (footprint "RESC1005X40N")
      (description "Resistor")
      (fields (field (name "PART NUMBER") "R0402_NO-VALUE") (field (name "AUTHOR") "CERN DEM JLC"))
      (libsource (lib "Resistors") (part "Resistor"))
    )
    (comp (ref "R56")
      (value "TC33X-2-105E")
      (footprint "BOUR-TC33X-2_V")
      (description "Trimming Potentiometer, 1M Ohm, -40 to 100 degC, 3-Pin SMD, RoHS, Tape and Reel")
      (fields
        (field (name "TOLERANCE") "25%")
        (field (name "RESISTANCE") "1MOhm")
        (field (name "MANUFACTURER") "Bourns")
      )
      (libsource (lib "LIBRARY_SCH") (part "TRIMPOT_TC33X_1M"))
    )
    (comp (ref "R57")
      (value "Undefined")
      (footprint "RESC1005X40N")
      (description "Resistor")
      (fields (field (name "PART NUMBER") "R0402_NO-VALUE") (field (name "AUTHOR") "CERN DEM JLC"))
      (libsource (lib "Resistors") (part "Resistor"))
    )
    (comp (ref "R58")
      (value "10k")
      (footprint "RESC1005X40N")
      (description "Resistor - 1%")
      (fields
        (field (name "PART NUMBER") "R0402_10K_1%_0.0625W_100PPM")
        (field (name "POWER") "0.0625W")
        (field (name "AUTHOR") "CERN DEM JLC")
      )
      (libsource (lib "Resistors") (part "Resistor - 1%"))
    )
    (comp (ref "R60")
      (value "0")
      (footprint "RESC1005X40N")
      (description "Resistor")
      (fields
        (field (name "PART NUMBER") "R0402_0R_JUMPER")
        (field (name "MANUFACTURER") "GENERIC")
        (field (name "AUTHOR") "CERN DEM JLC")
      )
      (libsource (lib "Resistors") (part "Resistor"))
    )
    (comp (ref "R61")
      (value "39k")
      (footprint "RESC1005X40N")
      (description "Resistor - 1%")
      (fields
        (field (name "PART NUMBER") "R0402_39K_1%_0.0625W_100PPM")
        (field (name "POWER") "0.0625W")
        (field (name "AUTHOR") "CERN DEM JLC")
      )
      (libsource (lib "Resistors") (part "Resistor - 1%"))
    )
    (comp (ref "R63")
      (value "10k")
      (footprint "RESC1005X40N")
      (description "Resistor - 1%")
      (fields
        (field (name "PART NUMBER") "R0402_10K_1%_0.0625W_100PPM")
        (field (name "POWER") "0.0625W")
        (field (name "AUTHOR") "CERN DEM JLC")
      )
      (libsource (lib "Resistors") (part "Resistor - 1%"))
    )
    (comp (ref "R64")
      (value "0R22")
      (footprint "RESC3216X70N")
      (description "Resistor - 1%")
      (fields
        (field (name "PART NUMBER") "R1206_0R22_1%_0.5W_100PPM")
        (field (name "POWER") "0.5W")
        (field (name "AUTHOR") "CERN DEM JLC")
      )
      (libsource (lib "Resistors") (part "Resistor - 1%"))
    )
    (comp (ref "R65")
      (value "100k")
      (footprint "RESC1005X40N")
      (description "Resistor - 1%")
      (fields
        (field (name "PART NUMBER") "R0402_100K_1%_0.0625W_100PPM")
        (field (name "POWER") "0.0625W")
        (field (name "AUTHOR") "CERN DEM JLC")
      )
      (libsource (lib "Resistors") (part "Resistor - 1%"))
    )
    (comp (ref "R70")
      (value "10k")
      (footprint "RESC1005X40N")
      (description "Resistor - 1%")
      (fields
        (field (name "PART NUMBER") "R0402_10K_1%_0.0625W_100PPM")
        (field (name "POWER") "0.0625W")
        (field (name "AUTHOR") "CERN DEM JLC")
      )
      (libsource (lib "Resistors") (part "Resistor - 1%"))
    )
    (comp (ref "R72")
      (value "18k")
      (footprint "RESC1005X40N")
      (description "Resistor - 1%")
      (fields
        (field (name "PART NUMBER") "R0402_18K_1%_0.0625W_100PPM")
        (field (name "POWER") "0.0625W")
        (field (name "AUTHOR") "CERN DEM JLC")
      )
      (libsource (lib "Resistors") (part "Resistor - 1%"))
    )
    (comp (ref "R73")
      (value "240k")
      (footprint "RESC1005X40N")
      (description "Resistor - 1%")
      (fields
        (field (name "PART NUMBER") "R0402_240K_1%_0.0625W_100PPM")
        (field (name "POWER") "0.0625W")
        (field (name "AUTHOR") "CERN DEM JLC")
      )
      (libsource (lib "Resistors") (part "Resistor - 1%"))
    )
    (comp (ref "R76")
      (value "68k")
      (footprint "RESC1005X40N")
      (description "Resistor - 1%")
      (fields
        (field (name "PART NUMBER") "R0402_68K_1%_0.0625W_100PPM")
        (field (name "POWER") "0.0625W")
        (field (name "AUTHOR") "CERN DEM JLC")
      )
      (libsource (lib "Resistors") (part "Resistor - 1%"))
    )
    (comp (ref "R79")
      (value "24k")
      (footprint "RESC1005X40N")
      (description "Resistor - 1%")
      (fields
        (field (name "PART NUMBER") "R0402_24K_1%_0.0625W_100PPM")
        (field (name "POWER") "0.0625W")
        (field (name "AUTHOR") "CERN DEM JLC")
      )
      (libsource (lib "Resistors") (part "Resistor - 1%"))
    )
    (comp (ref "R80")
      (value "75k")
      (footprint "RESC1005X40N")
      (description "Resistor - 1%")
      (fields
        (field (name "PART NUMBER") "R0402_75K_1%_0.0625W_100PPM")
        (field (name "POWER") "0.0625W")
        (field (name "AUTHOR") "CERN DEM JLC")
      )
      (libsource (lib "Resistors") (part "Resistor - 1%"))
    )
    (comp (ref "R81")
      (value "10k")
      (footprint "RESC1005X40N")
      (description "Resistor - 1%")
      (fields
        (field (name "PART NUMBER") "R0402_10K_1%_0.0625W_100PPM")
        (field (name "POWER") "0.0625W")
        (field (name "AUTHOR") "CERN DEM JLC")
      )
      (libsource (lib "Resistors") (part "Resistor - 1%"))
    )
    (comp (ref "R83")
      (value "10k")
      (footprint "RESC1005X40N")
      (description "Resistor - 1%")
      (fields
        (field (name "PART NUMBER") "R0402_10K_1%_0.0625W_100PPM")
        (field (name "POWER") "0.0625W")
        (field (name "AUTHOR") "CERN DEM JLC")
      )
      (libsource (lib "Resistors") (part "Resistor - 1%"))
    )
    (comp (ref "R85")
      (value "10k")
      (footprint "RESC1005X40N")
      (description "Resistor - 1%")
      (fields
        (field (name "PART NUMBER") "R0402_10K_1%_0.0625W_100PPM")
        (field (name "POWER") "0.0625W")
        (field (name "AUTHOR") "CERN DEM JLC")
      )
      (libsource (lib "Resistors") (part "Resistor - 1%"))
    )
    (comp (ref "R87")
      (value "100k")
      (footprint "RESC1005X40N")
      (description "Resistor - 1%")
      (fields
        (field (name "PART NUMBER") "R0402_100K_1%_0.0625W_100PPM")
        (field (name "POWER") "0.0625W")
        (field (name "AUTHOR") "CERN DEM JLC")
      )
      (libsource (lib "Resistors") (part "Resistor - 1%"))
    )
    (comp (ref "R88")
      (value "47k")
      (footprint "RESC1005X40N")
      (description "Resistor - 1%")
      (fields
        (field (name "PART NUMBER") "R0402_47K_1%_0.0625W_100PPM")
        (field (name "POWER") "0.0625W")
        (field (name "AUTHOR") "CERN DEM JLC")
      )
      (libsource (lib "Resistors") (part "Resistor - 1%"))
    )
    (comp (ref "R89")
      (value "0")
      (footprint "RESC1005X40N")
      (description "Resistor")
      (fields
        (field (name "PART NUMBER") "R0402_0R_JUMPER")
        (field (name "MANUFACTURER") "GENERIC")
        (field (name "AUTHOR") "CERN DEM JLC")
      )
      (libsource (lib "Resistors") (part "Resistor"))
    )
    (comp (ref "R90")
      (value "62k")
      (footprint "RESC1005X40N")
      (description "Resistor - 1%")
      (fields
        (field (name "PART NUMBER") "R0402_62K_1%_0.0625W_100PPM")
        (field (name "POWER") "0.0625W")
        (field (name "AUTHOR") "CERN DEM JLC")
      )
      (libsource (lib "Resistors") (part "Resistor - 1%"))
    )
    (comp (ref "R91")
      (value "68k")
      (footprint "RESC1005X40N")
      (description "Resistor - 1%")
      (fields
        (field (name "PART NUMBER") "R0402_68K_1%_0.0625W_100PPM")
        (field (name "POWER") "0.0625W")
        (field (name "AUTHOR") "CERN DEM JLC")
      )
      (libsource (lib "Resistors") (part "Resistor - 1%"))
    )
    (comp (ref "R93")
      (value "18k")
      (footprint "RESC1005X40N")
      (description "Resistor - 1%")
      (fields
        (field (name "PART NUMBER") "R0402_18K_1%_0.0625W_100PPM")
        (field (name "POWER") "0.0625W")
        (field (name "AUTHOR") "CERN DEM JLC")
      )
      (libsource (lib "Resistors") (part "Resistor - 1%"))
    )
    (comp (ref "R94")
      (value "68k")
      (footprint "RESC1005X40N")
      (description "Resistor - 1%")
      (fields
        (field (name "PART NUMBER") "R0402_68K_1%_0.0625W_100PPM")
        (field (name "POWER") "0.0625W")
        (field (name "AUTHOR") "CERN DEM JLC")
      )
      (libsource (lib "Resistors") (part "Resistor - 1%"))
    )
    (comp (ref "R97")
      (value "10k")
      (footprint "RESC1005X40N")
      (description "Resistor - 1%")
      (fields
        (field (name "PART NUMBER") "R0402_10K_1%_0.0625W_100PPM")
        (field (name "POWER") "0.0625W")
        (field (name "AUTHOR") "CERN DEM JLC")
      )
      (libsource (lib "Resistors") (part "Resistor - 1%"))
    )
    (comp (ref "R107")
      (value "10k")
      (footprint "RESC1005X40N")
      (description "Resistor - 1%")
      (fields
        (field (name "PART NUMBER") "R0402_10K_1%_0.0625W_100PPM")
        (field (name "POWER") "0.0625W")
        (field (name "AUTHOR") "CERN DEM JLC")
      )
      (libsource (lib "Resistors") (part "Resistor - 1%"))
    )
    (comp (ref "R110")
      (value "100k")
      (footprint "RESC1005X40N")
      (description "Resistor - 1%")
      (fields
        (field (name "PART NUMBER") "R0402_100K_1%_0.0625W_100PPM")
        (field (name "POWER") "0.0625W")
        (field (name "AUTHOR") "CERN DEM JLC")
      )
      (libsource (lib "Resistors") (part "Resistor - 1%"))
    )
    (comp (ref "R156")
      (value "100k")
      (footprint "RESC1005X40N")
      (description "Resistor - 1%")
      (fields
        (field (name "PART NUMBER") "R0402_100K_1%_0.0625W_100PPM")
        (field (name "POWER") "0.0625W")
        (field (name "AUTHOR") "CERN DEM JLC")
      )
      (libsource (lib "Resistors") (part "Resistor - 1%"))
    )
    (comp (ref "R192")
      (value "3k6")
      (footprint "RESC1005X40N")
      (description "Resistor - 1%")
      (fields
        (field (name "PART NUMBER") "R0402_3K6_1%_0.0625W_100PPM")
        (field (name "POWER") "0.0625W")
        (field (name "AUTHOR") "CERN DEM JLC")
      )
      (libsource (lib "Resistors") (part "Resistor - 1%"))
    )
    (comp (ref "R193")
      (value "24k")
      (footprint "RESC1005X40N")
      (description "Resistor - 1%")
      (fields
        (field (name "PART NUMBER") "R0402_24K_1%_0.0625W_100PPM")
        (field (name "POWER") "0.0625W")
        (field (name "AUTHOR") "CERN DEM JLC")
      )
      (libsource (lib "Resistors") (part "Resistor - 1%"))
    )
    (comp (ref "R194")
      (value "24k")
      (footprint "RESC1005X40N")
      (description "Resistor - 1%")
      (fields
        (field (name "PART NUMBER") "R0402_24K_1%_0.0625W_100PPM")
        (field (name "POWER") "0.0625W")
        (field (name "AUTHOR") "CERN DEM JLC")
      )
      (libsource (lib "Resistors") (part "Resistor - 1%"))
    )
    (comp (ref "R195")
      (value "24k")
      (footprint "RESC1005X40N")
      (description "Resistor - 1%")
      (fields
        (field (name "PART NUMBER") "R0402_24K_1%_0.0625W_100PPM")
        (field (name "POWER") "0.0625W")
        (field (name "AUTHOR") "CERN DEM JLC")
      )
      (libsource (lib "Resistors") (part "Resistor - 1%"))
    )
    (comp (ref "T3")
      (value "2N7002BKS")
      (footprint "SOT65P210X110-6N")
      (description "60V, 300mA Dual N-Channel Trench MOSFET")
      (fields
        (field (name "MANUFACTURER") "NXP SEMICONDUCTORS")
        (field (name "MANUFACTURER PART NUMBER") "2N7002BKS6")
        (field (name "AUTHOR") "CERN DEM JLC")
      )
      (libsource (lib "ICs And Semiconductors") (part "2N7002BKS"))
    )
    (comp (ref "TP9")
      (value "Test Point")
      (footprint "TPS127")
      (fields (field (name "PART NUMBER") "SMD_PAD_1.27X1.27MM") (field (name "AUTHOR") "CERN DEM JLC"))
      (libsource (lib "Eletro-mechanical") (part "Test Point"))
    )
    (comp (ref "TP10")
      (value "Test Point")
      (footprint "TPS127")
      (fields (field (name "PART NUMBER") "SMD_PAD_1.27X1.27MM") (field (name "AUTHOR") "CERN DEM JLC"))
      (libsource (lib "Eletro-mechanical") (part "Test Point"))
    )
    (comp (ref "TP11")
      (value "Test Point")
      (footprint "TPS127")
      (fields (field (name "PART NUMBER") "SMD_PAD_1.27X1.27MM") (field (name "AUTHOR") "CERN DEM JLC"))
      (libsource (lib "Eletro-mechanical") (part "Test Point"))
    )
    (comp (ref "TP13")
      (value "Test Point")
      (footprint "TPS127")
      (fields (field (name "PART NUMBER") "SMD_PAD_1.27X1.27MM") (field (name "AUTHOR") "CERN DEM JLC"))
      (libsource (lib "Eletro-mechanical") (part "Test Point"))
    )
    (comp (ref "TP14")
      (value "Test Point")
      (footprint "TPS127")
      (fields (field (name "PART NUMBER") "SMD_PAD_1.27X1.27MM") (field (name "AUTHOR") "CERN DEM JLC"))
      (libsource (lib "Eletro-mechanical") (part "Test Point"))
    )
    (comp (ref "U1")
      (value "LT8610IMSE")
      (footprint "LT-MSE-16-EDP_L")
      (fields (field (name "MANUFACTURER") "Linear Technology"))
      (libsource (lib "Altium Content Vault") (part "LT-LT8610-MSE-16"))
    )
    (comp (ref "U6")
      (value "LT8610IMSE")
      (footprint "LT-MSE-16-EDP_L")
      (fields (field (name "MANUFACTURER") "Linear Technology"))
      (libsource (lib "Altium Content Vault") (part "LT-LT8610-MSE-16"))
    )
    (comp (ref "U7")
      (value "LT8610IMSE")
      (footprint "LT-MSE-16-EDP_L")
      (fields (field (name "MANUFACTURER") "Linear Technology"))
      (libsource (lib "Altium Content Vault") (part "LT-LT8610-MSE-16"))
    )
  )
  (nets
    (net (code "6") (name "/3P3V") (class "Default")
      (node (ref "L10") (pin "2") (pinfunction "2_2") (pintype "passive"))
    )
    (net (code "7") (name "/3P3VAUX") (class "Default")
      (node (ref "L3") (pin "2") (pinfunction "2_2") (pintype "passive"))
    )
    (net (code "8") (name "/12P0V") (class "Default")
      (node (ref "L8") (pin "2") (pinfunction "2_2") (pintype "passive"))
    )
    (net (code "9") (name "/DIS_LVDS") (class "Default")
      (node (ref "R85") (pin "2") (pinfunction "2_2") (pintype "passive"))
      (node (ref "T3") (pin "3") (pinfunction "D_3") (pintype "passive"))
    )
    (net (code "10") (name "/EN_IFC") (class "Default")
      (node (ref "D7") (pin "2") (pinfunction "A_2") (pintype "passive"))
      (node (ref "R110") (pin "1") (pinfunction "1_1") (pintype "passive"))
    )
    (net (code "11") (name "/EN_P2V5") (class "Default")
      (node (ref "R60") (pin "2") (pinfunction "2_2") (pintype "passive"))
      (node (ref "U6") (pin "4") (pinfunction "EN/UV_4") (pintype "input"))
    )
    (net (code "12") (name "/EN_P3V3") (class "Default")
      (node (ref "R89") (pin "2") (pinfunction "2_2") (pintype "passive"))
      (node (ref "U7") (pin "4") (pinfunction "EN/UV_4") (pintype "input"))
    )
    (net (code "13") (name "/FMC_P12V0_MSP430") (class "Default")
      (node (ref "R63") (pin "1") (pinfunction "1_1") (pintype "passive"))
    )
    (net (code "14") (name "/FMC_P12V0_ONn") (class "Default")
      (node (ref "IC9") (pin "4") (pinfunction "~{ON}_4") (pintype "input"))
      (node (ref "R63") (pin "2") (pinfunction "2_2") (pintype "passive"))
      (node (ref "R83") (pin "2") (pinfunction "2_2") (pintype "passive"))
    )
    (net (code "15") (name "/FMC_P12V0_OVCn") (class "Default")
      (node (ref "IC9") (pin "7") (pinfunction "~{FLAGB}_7") (pintype "open_collector"))
      (node (ref "R81") (pin "2") (pinfunction "2_2") (pintype "passive"))
    )
    (net (code "16") (name "/Imeas_P2V5") (class "Default")
      (node (ref "C25") (pin "2") (pinfunction "2_2") (pintype "passive"))
      (node (ref "IC7") (pin "8") (pinfunction "IN-_8") (pintype "input"))
      (node (ref "R26") (pin "1") (pinfunction "1_1") (pintype "passive"))
    )
    (net (code "17") (name "/Imeas_P3V3") (class "Default")
      (node (ref "C26") (pin "2") (pinfunction "2_2") (pintype "passive"))
      (node (ref "IC7") (pin "10") (pinfunction "IN-_10") (pintype "input"))
      (node (ref "R27") (pin "1") (pinfunction "1_1") (pintype "passive"))
    )
    (net (code "18") (name "/Imeas_P3V3MP") (class "Default")
      (node (ref "C205") (pin "2") (pinfunction "2_2") (pintype "passive"))
      (node (ref "R97") (pin "1") (pinfunction "1_1") (pintype "passive"))
    )
    (net (code "19") (name "/Imeas_P5V0") (class "Default")
      (node (ref "C22") (pin "2") (pinfunction "2_2") (pintype "passive"))
      (node (ref "IC7") (pin "4") (pinfunction "IN-_4") (pintype "input"))
      (node (ref "R47") (pin "1") (pinfunction "1_1") (pintype "passive"))
    )
    (net (code "20") (name "/Imeas_P12V0") (class "Default")
      (node (ref "C75") (pin "2") (pinfunction "2_2") (pintype "passive"))
      (node (ref "R45") (pin "1") (pinfunction "1_1") (pintype "passive"))
    )
    (net (code "21") (name "/MAIN_PWR_ON") (class "Default")
      (node (ref "IC6") (pin "4") (pinfunction "~{ON}_4") (pintype "input"))
      (node (ref "R13") (pin "2") (pinfunction "2_2") (pintype "passive"))
    )
    (net (code "22") (name "/P2V5") (class "Default")
      (node (ref "IC8") (pin "5") (pinfunction "RS-_5") (pintype "passive"))
      (node (ref "L9") (pin "1") (pinfunction "1_1") (pintype "passive"))
      (node (ref "R15") (pin "2") (pinfunction "2_2") (pintype "passive"))
      (node (ref "R79") (pin "1") (pinfunction "1_1") (pintype "passive"))
      (node (ref "TP13") (pin "1") (pinfunction "1_1") (pintype "bidirectional"))
    )
    (net (code "23") (name "/P3V3") (class "Default")
      (node (ref "IC12") (pin "5") (pinfunction "RS-_5") (pintype "passive"))
      (node (ref "L10") (pin "1") (pinfunction "1_1") (pintype "passive"))
      (node (ref "L3") (pin "1") (pinfunction "1_1") (pintype "passive"))
      (node (ref "R110") (pin "2") (pinfunction "2_2") (pintype "passive"))
      (node (ref "R22") (pin "2") (pinfunction "2_2") (pintype "passive"))
      (node (ref "R81") (pin "1") (pinfunction "1_1") (pintype "passive"))
      (node (ref "R83") (pin "1") (pinfunction "1_1") (pintype "passive"))
      (node (ref "R88") (pin "2") (pinfunction "2_2") (pintype "passive"))
      (node (ref "TP14") (pin "1") (pinfunction "1_1") (pintype "bidirectional"))
    )
    (net (code "24") (name "/P3V3MP") (class "Default")
      (node (ref "IC2") (pin "5") (pinfunction "RS-_5") (pintype "passive"))
      (node (ref "R11") (pin "1") (pinfunction "1_1") (pintype "passive"))
      (node (ref "R64") (pin "2") (pinfunction "2_2") (pintype "passive"))
      (node (ref "R70") (pin "2") (pinfunction "2_2") (pintype "passive"))
      (node (ref "R87") (pin "1") (pinfunction "1_1") (pintype "passive"))
      (node (ref "TP11") (pin "1") (pinfunction "1_1") (pintype "bidirectional"))
    )
    (net (code "25") (name "/P5V0") (class "Default")
      (node (ref "IC5") (pin "5") (pinfunction "RS-_5") (pintype "passive"))
      (node (ref "R20") (pin "2") (pinfunction "2_2") (pintype "passive"))
      (node (ref "R24") (pin "2") (pinfunction "2_2") (pintype "passive"))
      (node (ref "TP10") (pin "1") (pinfunction "1_1") (pintype "bidirectional"))
    )
    (net (code "26") (name "/P5V0_buck") (class "Default")
      (node (ref "C213") (pin "2") (pinfunction "2_2") (pintype "passive"))
      (node (ref "C35") (pin "2") (pinfunction "2_2") (pintype "passive"))
      (node (ref "C7") (pin "2") (pinfunction "2_2") (pintype "passive"))
      (node (ref "C72") (pin "2") (pinfunction "2_2") (pintype "passive"))
      (node (ref "C9") (pin "2") (pinfunction "2_2") (pintype "passive"))
      (node (ref "IC5") (pin "4") (pinfunction "RS+_4") (pintype "passive"))
      (node (ref "L1") (pin "2") (pinfunction "2_2") (pintype "passive"))
      (node (ref "R2") (pin "2") (pinfunction "2_2") (pintype "passive"))
      (node (ref "R20") (pin "1") (pinfunction "1_1") (pintype "passive"))
    )
    (net (code "27") (name "/P12V0") (class "Default")
      (node (ref "C1") (pin "2") (pinfunction "2_2") (pintype "passive"))
      (node (ref "C10") (pin "2") (pinfunction "2_2") (pintype "passive"))
      (node (ref "C12") (pin "2") (pinfunction "2_2") (pintype "passive"))
      (node (ref "C18") (pin "2") (pinfunction "2_2") (pintype "passive"))
      (node (ref "C269") (pin "2") (pinfunction "2_2") (pintype "passive"))
      (node (ref "C270") (pin "2") (pinfunction "2_2") (pintype "passive"))
      (node (ref "C29") (pin "2") (pinfunction "2_2") (pintype "passive"))
      (node (ref "C5") (pin "2") (pinfunction "2_2") (pintype "passive"))
      (node (ref "IC12") (pin "3") (pinfunction "VCC_3") (pintype "passive"))
      (node (ref "IC5") (pin "3") (pinfunction "VCC_3") (pintype "passive"))
      (node (ref "IC6") (pin "8") (pinfunction "VOUT_8") (pintype "passive"))
      (node (ref "IC7") (pin "3") (pinfunction "V+_3") (pintype "power_in"))
      (node (ref "IC8") (pin "3") (pinfunction "VCC_3") (pintype "passive"))
      (node (ref "R1") (pin "1") (pinfunction "1_1") (pintype "passive"))
      (node (ref "R107") (pin "1") (pinfunction "1_1") (pintype "passive"))
      (node (ref "R23") (pin "1") (pinfunction "1_1") (pintype "passive"))
      (node (ref "R3") (pin "2") (pinfunction "2_2") (pintype "passive"))
      (node (ref "R46") (pin "3") (pinfunction "3_3") (pintype "passive"))
      (node (ref "R52") (pin "2") (pinfunction "2_2") (pintype "passive"))
      (node (ref "R53") (pin "3") (pinfunction "3_3") (pintype "passive"))
      (node (ref "R55") (pin "2") (pinfunction "2_2") (pintype "passive"))
      (node (ref "R56") (pin "3") (pinfunction "3_3") (pintype "passive"))
      (node (ref "R58") (pin "2") (pinfunction "2_2") (pintype "passive"))
      (node (ref "R76") (pin "2") (pinfunction "2_2") (pintype "passive"))
      (node (ref "R85") (pin "1") (pinfunction "1_1") (pintype "passive"))
      (node (ref "R94") (pin "2") (pinfunction "2_2") (pintype "passive"))
      (node (ref "U1") (pin "5") (pinfunction "VIN_5") (pintype "power_in"))
      (node (ref "U1") (pin "6") (pinfunction "VIN_6") (pintype "power_in"))
      (node (ref "U6") (pin "5") (pinfunction "VIN_5") (pintype "power_in"))
      (node (ref "U6") (pin "6") (pinfunction "VIN_6") (pintype "power_in"))
      (node (ref "U7") (pin "5") (pinfunction "VIN_5") (pintype "power_in"))
      (node (ref "U7") (pin "6") (pinfunction "VIN_6") (pintype "power_in"))
    )
    (net (code "28") (name "/PG_P2V5") (class "Default")
      (node (ref "D6") (pin "1") (pinfunction "C_1") (pintype "passive"))
      (node (ref "R194") (pin "2") (pinfunction "2_2") (pintype "passive"))
      (node (ref "R76") (pin "1") (pinfunction "1_1") (pintype "passive"))
      (node (ref "U6") (pin "15") (pinfunction "PG_15") (pintype "tri_state"))
    )
    (net (code "29") (name "/PG_P3V3") (class "Default")
      (node (ref "D17") (pin "1") (pinfunction "C_1") (pintype "passive"))
      (node (ref "R193") (pin "2") (pinfunction "2_2") (pintype "passive"))
      (node (ref "R94") (pin "1") (pinfunction "1_1") (pintype "passive"))
      (node (ref "U7") (pin "15") (pinfunction "PG_15") (pintype "tri_state"))
    )
    (net (code "30") (name "/PG_P5V0") (class "Default")
      (node (ref "R195") (pin "2") (pinfunction "2_2") (pintype "passive"))
      (node (ref "R58") (pin "1") (pinfunction "1_1") (pintype "passive"))
      (node (ref "R60") (pin "1") (pinfunction "1_1") (pintype "passive"))
      (node (ref "U1") (pin "15") (pinfunction "PG_15") (pintype "tri_state"))
    )
    (net (code "31") (name "/PWR_OVLn") (class "Default")
      (node (ref "C83") (pin "2") (pinfunction "2_2") (pintype "passive"))
      (node (ref "IC7") (pin "13") (pinfunction "OUT_13") (pintype "output"))
      (node (ref "IC7") (pin "14") (pinfunction "OUT_14") (pintype "output"))
      (node (ref "IC7") (pin "2") (pinfunction "OUT_2") (pintype "output"))
      (node (ref "R192") (pin "2") (pinfunction "2_2") (pintype "passive"))
      (node (ref "R23") (pin "2") (pinfunction "2_2") (pintype "passive"))
      (node (ref "R5") (pin "2") (pinfunction "2_2") (pintype "passive"))
    )
    (net (code "32") (name "/SYNC") (class "Default")
      (node (ref "R17") (pin "1") (pinfunction "1_1") (pintype "passive"))
      (node (ref "R25") (pin "1") (pinfunction "1_1") (pintype "passive"))
      (node (ref "R4") (pin "1") (pinfunction "1_1") (pintype "passive"))
    )
    (net (code "33") (name "/Umeas_P2V5") (class "Default")
      (node (ref "C86") (pin "2") (pinfunction "2_2") (pintype "passive"))
      (node (ref "R79") (pin "2") (pinfunction "2_2") (pintype "passive"))
      (node (ref "R80") (pin "2") (pinfunction "2_2") (pintype "passive"))
    )
    (net (code "34") (name "/Umeas_P3V3") (class "Default")
      (node (ref "C87") (pin "2") (pinfunction "2_2") (pintype "passive"))
      (node (ref "R88") (pin "1") (pinfunction "1_1") (pintype "passive"))
      (node (ref "R90") (pin "2") (pinfunction "2_2") (pintype "passive"))
    )
    (net (code "35") (name "/Umeas_P3V3MP") (class "Default")
      (node (ref "C166") (pin "2") (pinfunction "2_2") (pintype "passive"))
      (node (ref "R87") (pin "2") (pinfunction "2_2") (pintype "passive"))
      (node (ref "R93") (pin "2") (pinfunction "2_2") (pintype "passive"))
    )
    (net (code "36") (name "/Umeas_P5V0") (class "Default")
      (node (ref "C82") (pin "2") (pinfunction "2_2") (pintype "passive"))
      (node (ref "R24") (pin "1") (pinfunction "1_1") (pintype "passive"))
    )
    (net (code "37") (name "/Umeas_P12V0") (class "Default")
      (node (ref "C23") (pin "2") (pinfunction "2_2") (pintype "passive"))
      (node (ref "R65") (pin "2") (pinfunction "2_2") (pintype "passive"))
      (node (ref "R72") (pin "2") (pinfunction "2_2") (pintype "passive"))
    )
    (net (code "38") (name "/Umeas_P12V0IN") (class "Default")
      (node (ref "C11") (pin "2") (pinfunction "2_2") (pintype "passive"))
      (node (ref "R1") (pin "2") (pinfunction "2_2") (pintype "passive"))
      (node (ref "R10") (pin "2") (pinfunction "2_2") (pintype "passive"))
    )
    (net (code "39") (name "/VADJ") (class "Default")
      (node (ref "L9") (pin "2") (pinfunction "2_2") (pintype "passive"))
    )
    (net (code "40") (name "/VIO_B_M2C") (class "Default")
      (node (ref "R156") (pin "2") (pinfunction "2_2") (pintype "passive"))
    )
    (net (code "46") (name "3.3V_AUX") (class "Default")
      (node (ref "C204") (pin "2") (pinfunction "2_2") (pintype "passive"))
      (node (ref "IC2") (pin "3") (pinfunction "VCC_3") (pintype "passive"))
      (node (ref "IC2") (pin "4") (pinfunction "RS+_4") (pintype "passive"))
      (node (ref "R64") (pin "1") (pinfunction "1_1") (pintype "passive"))
    )
    (net (code "47") (name "GND") (class "Default")
      (node (ref "C1") (pin "1") (pinfunction "1_1") (pintype "passive"))
      (node (ref "C10") (pin "1") (pinfunction "1_1") (pintype "passive"))
      (node (ref "C11") (pin "1") (pinfunction "1_1") (pintype "passive"))
      (node (ref "C12") (pin "1") (pinfunction "1_1") (pintype "passive"))
      (node (ref "C166") (pin "1") (pinfunction "1_1") (pintype "passive"))
      (node (ref "C18") (pin "1") (pinfunction "1_1") (pintype "passive"))
      (node (ref "C20") (pin "1") (pinfunction "1_1") (pintype "passive"))
      (node (ref "C204") (pin "1") (pinfunction "1_1") (pintype "passive"))
      (node (ref "C205") (pin "1") (pinfunction "1_1") (pintype "passive"))
      (node (ref "C21") (pin "1") (pinfunction "1_1") (pintype "passive"))
      (node (ref "C213") (pin "1") (pinfunction "1_1") (pintype "passive"))
      (node (ref "C214") (pin "1") (pinfunction "1_1") (pintype "passive"))
      (node (ref "C215") (pin "1") (pinfunction "1_1") (pintype "passive"))
      (node (ref "C216") (pin "1") (pinfunction "1_1") (pintype "passive"))
      (node (ref "C22") (pin "1") (pinfunction "1_1") (pintype "passive"))
      (node (ref "C23") (pin "1") (pinfunction "1_1") (pintype "passive"))
      (node (ref "C24") (pin "1") (pinfunction "1_1") (pintype "passive"))
      (node (ref "C25") (pin "1") (pinfunction "1_1") (pintype "passive"))
      (node (ref "C26") (pin "1") (pinfunction "1_1") (pintype "passive"))
      (node (ref "C269") (pin "1") (pinfunction "1_1") (pintype "passive"))
      (node (ref "C27") (pin "1") (pinfunction "1_1") (pintype "passive"))
      (node (ref "C270") (pin "1") (pinfunction "1_1") (pintype "passive"))
      (node (ref "C28") (pin "1") (pinfunction "1_1") (pintype "passive"))
      (node (ref "C29") (pin "1") (pinfunction "1_1") (pintype "passive"))
      (node (ref "C31") (pin "1") (pinfunction "1_1") (pintype "passive"))
      (node (ref "C32") (pin "1") (pinfunction "1_1") (pintype "passive"))
      (node (ref "C35") (pin "1") (pinfunction "1_1") (pintype "passive"))
      (node (ref "C5") (pin "1") (pinfunction "1_1") (pintype "passive"))
      (node (ref "C72") (pin "1") (pinfunction "1_1") (pintype "passive"))
      (node (ref "C74") (pin "1") (pinfunction "1_1") (pintype "passive"))
      (node (ref "C75") (pin "1") (pinfunction "1_1") (pintype "passive"))
      (node (ref "C78") (pin "1") (pinfunction "1_1") (pintype "passive"))
      (node (ref "C79") (pin "1") (pinfunction "1_1") (pintype "passive"))
      (node (ref "C8") (pin "1") (pinfunction "1_1") (pintype "passive"))
      (node (ref "C82") (pin "1") (pinfunction "1_1") (pintype "passive"))
      (node (ref "C83") (pin "1") (pinfunction "1_1") (pintype "passive"))
      (node (ref "C86") (pin "1") (pinfunction "1_1") (pintype "passive"))
      (node (ref "C87") (pin "1") (pinfunction "1_1") (pintype "passive"))
      (node (ref "C9") (pin "1") (pinfunction "1_1") (pintype "passive"))
      (node (ref "IC12") (pin "1") (pinfunction "GND_1") (pintype "passive"))
      (node (ref "IC2") (pin "1") (pinfunction "GND_1") (pintype "passive"))
      (node (ref "IC4") (pin "1") (pinfunction "GND_1") (pintype "passive"))
      (node (ref "IC5") (pin "1") (pinfunction "GND_1") (pintype "passive"))
      (node (ref "IC6") (pin "2") (pinfunction "PGOOD_2") (pintype "open_collector"))
      (node (ref "IC6") (pin "5") (pinfunction "GND_5") (pintype "power_in"))
      (node (ref "IC7") (pin "12") (pinfunction "V-_12") (pintype "power_in"))
      (node (ref "IC8") (pin "1") (pinfunction "GND_1") (pintype "passive"))
      (node (ref "IC9") (pin "2") (pinfunction "PGOOD_2") (pintype "open_collector"))
      (node (ref "IC9") (pin "5") (pinfunction "GND_5") (pintype "power_in"))
      (node (ref "R10") (pin "1") (pinfunction "1_1") (pintype "passive"))
      (node (ref "R12") (pin "1") (pinfunction "1_1") (pintype "passive"))
      (node (ref "R13") (pin "1") (pinfunction "1_1") (pintype "passive"))
      (node (ref "R156") (pin "1") (pinfunction "1_1") (pintype "passive"))
      (node (ref "R18") (pin "1") (pinfunction "1_1") (pintype "passive"))
      (node (ref "R192") (pin "1") (pinfunction "1_1") (pintype "passive"))
      (node (ref "R193") (pin "1") (pinfunction "1_1") (pintype "passive"))
      (node (ref "R194") (pin "1") (pinfunction "1_1") (pintype "passive"))
      (node (ref "R195") (pin "1") (pinfunction "1_1") (pintype "passive"))
      (node (ref "R21") (pin "1") (pinfunction "1_1") (pintype "passive"))
      (node (ref "R29") (pin "1") (pinfunction "1_1") (pintype "passive"))
      (node (ref "R30") (pin "1") (pinfunction "1_1") (pintype "passive"))
      (node (ref "R46") (pin "1") (pinfunction "1_1") (pintype "passive"))
      (node (ref "R48") (pin "1") (pinfunction "1_1") (pintype "passive"))
      (node (ref "R53") (pin "1") (pinfunction "1_1") (pintype "passive"))
      (node (ref "R54") (pin "1") (pinfunction "1_1") (pintype "passive"))
      (node (ref "R56") (pin "1") (pinfunction "1_1") (pintype "passive"))
      (node (ref "R57") (pin "1") (pinfunction "1_1") (pintype "passive"))
      (node (ref "R61") (pin "1") (pinfunction "1_1") (pintype "passive"))
      (node (ref "R7") (pin "1") (pinfunction "1_1") (pintype "passive"))
      (node (ref "R70") (pin "1") (pinfunction "1_1") (pintype "passive"))
      (node (ref "R72") (pin "1") (pinfunction "1_1") (pintype "passive"))
      (node (ref "R73") (pin "1") (pinfunction "1_1") (pintype "passive"))
      (node (ref "R80") (pin "1") (pinfunction "1_1") (pintype "passive"))
      (node (ref "R90") (pin "1") (pinfunction "1_1") (pintype "passive"))
      (node (ref "R93") (pin "1") (pinfunction "1_1") (pintype "passive"))
      (node (ref "T3") (pin "4") (pinfunction "S_4") (pintype "passive"))
      (node (ref "U1") (pin "17") (pinfunction "EP_17") (pintype "power_in"))
      (node (ref "U1") (pin "7") (pinfunction "PGND_7") (pintype "power_in"))
      (node (ref "U1") (pin "8") (pinfunction "PGND_8") (pintype "power_in"))
      (node (ref "U6") (pin "17") (pinfunction "EP_17") (pintype "power_in"))
      (node (ref "U6") (pin "7") (pinfunction "PGND_7") (pintype "power_in"))
      (node (ref "U6") (pin "8") (pinfunction "PGND_8") (pintype "power_in"))
      (node (ref "U7") (pin "17") (pinfunction "EP_17") (pintype "power_in"))
      (node (ref "U7") (pin "7") (pinfunction "PGND_7") (pintype "power_in"))
      (node (ref "U7") (pin "8") (pinfunction "PGND_8") (pintype "power_in"))
    )
    (net (code "48") (name "Net-(C6-Pad2)") (class "Default")
      (node (ref "C6") (pin "2") (pinfunction "2_2") (pintype "passive"))
      (node (ref "L1") (pin "1") (pinfunction "1_1") (pintype "passive"))
      (node (ref "U1") (pin "10") (pinfunction "SW_10") (pintype "power_in"))
      (node (ref "U1") (pin "11") (pinfunction "SW_11") (pintype "power_in"))
      (node (ref "U1") (pin "9") (pinfunction "SW_9") (pintype "power_in"))
    )
    (net (code "49") (name "Net-(C19-Pad2)") (class "Default")
      (node (ref "C19") (pin "2") (pinfunction "2_2") (pintype "passive"))
      (node (ref "L4") (pin "1") (pinfunction "1_1") (pintype "passive"))
      (node (ref "U6") (pin "10") (pinfunction "SW_10") (pintype "power_in"))
      (node (ref "U6") (pin "11") (pinfunction "SW_11") (pintype "power_in"))
      (node (ref "U6") (pin "9") (pinfunction "SW_9") (pintype "power_in"))
    )
    (net (code "50") (name "Net-(C30-Pad2)") (class "Default")
      (node (ref "C30") (pin "2") (pinfunction "2_2") (pintype "passive"))
      (node (ref "L6") (pin "1") (pinfunction "1_1") (pintype "passive"))
      (node (ref "U7") (pin "10") (pinfunction "SW_10") (pintype "power_in"))
      (node (ref "U7") (pin "11") (pinfunction "SW_11") (pintype "power_in"))
      (node (ref "U7") (pin "9") (pinfunction "SW_9") (pintype "power_in"))
    )
    (net (code "51") (name "Net-(D17-A)") (class "Default")
      (node (ref "D17") (pin "2") (pinfunction "A_2") (pintype "passive"))
      (node (ref "D6") (pin "2") (pinfunction "A_2") (pintype "passive"))
      (node (ref "D7") (pin "1") (pinfunction "C_1") (pintype "passive"))
      (node (ref "R107") (pin "2") (pinfunction "2_2") (pintype "passive"))
      (node (ref "T3") (pin "5") (pinfunction "G_5") (pintype "passive"))
    )
    (net (code "52") (name "Net-(IC2-OUT)") (class "Default")
      (node (ref "IC2") (pin "2") (pinfunction "OUT_2") (pintype "passive"))
      (node (ref "R97") (pin "2") (pinfunction "2_2") (pintype "passive"))
    )
    (net (code "53") (name "Net-(IC4-OUT)") (class "Default")
      (node (ref "IC4") (pin "2") (pinfunction "OUT_2") (pintype "passive"))
      (node (ref "R45") (pin "2") (pinfunction "2_2") (pintype "passive"))
    )
    (net (code "54") (name "Net-(IC4-RS+)") (class "Default")
      (node (ref "C8") (pin "2") (pinfunction "2_2") (pintype "passive"))
      (node (ref "IC4") (pin "4") (pinfunction "RS+_4") (pintype "passive"))
      (node (ref "IC9") (pin "8") (pinfunction "VOUT_8") (pintype "passive"))
      (node (ref "R9") (pin "1") (pinfunction "1_1") (pintype "passive"))
      (node (ref "TP9") (pin "1") (pinfunction "1_1") (pintype "bidirectional"))
    )
    (net (code "55") (name "Net-(IC4-RS-)") (class "Default")
      (node (ref "IC4") (pin "5") (pinfunction "RS-_5") (pintype "passive"))
      (node (ref "L8") (pin "1") (pinfunction "1_1") (pintype "passive"))
      (node (ref "R65") (pin "1") (pinfunction "1_1") (pintype "passive"))
      (node (ref "R9") (pin "2") (pinfunction "2_2") (pintype "passive"))
    )
    (net (code "56") (name "Net-(IC5-OUT)") (class "Default")
      (node (ref "IC5") (pin "2") (pinfunction "OUT_2") (pintype "passive"))
      (node (ref "R47") (pin "2") (pinfunction "2_2") (pintype "passive"))
    )
    (net (code "57") (name "Net-(IC6-ISET)") (class "Default")
      (node (ref "IC6") (pin "3") (pinfunction "ISET_3") (pintype "passive"))
      (node (ref "R12") (pin "2") (pinfunction "2_2") (pintype "passive"))
    )
    (net (code "58") (name "Net-(IC6-~{FLAGB})") (class "Default")
      (node (ref "IC6") (pin "7") (pinfunction "~{FLAGB}_7") (pintype "open_collector"))
      (node (ref "R11") (pin "2") (pinfunction "2_2") (pintype "passive"))
    )
    (net (code "59") (name "Net-(IC7A-IN+)") (class "Default")
      (node (ref "IC7") (pin "5") (pinfunction "IN+_5") (pintype "input"))
      (node (ref "R3") (pin "1") (pinfunction "1_1") (pintype "passive"))
      (node (ref "R46") (pin "2") (pinfunction "2_2") (pintype "passive"))
      (node (ref "R48") (pin "2") (pinfunction "2_2") (pintype "passive"))
    )
    (net (code "60") (name "Net-(IC7C-IN+)") (class "Default")
      (node (ref "IC7") (pin "9") (pinfunction "IN+_9") (pintype "input"))
      (node (ref "R52") (pin "1") (pinfunction "1_1") (pintype "passive"))
      (node (ref "R53") (pin "2") (pinfunction "2_2") (pintype "passive"))
      (node (ref "R54") (pin "2") (pinfunction "2_2") (pintype "passive"))
    )
    (net (code "61") (name "Net-(IC7D-IN+)") (class "Default")
      (node (ref "IC7") (pin "11") (pinfunction "IN+_11") (pintype "input"))
      (node (ref "R55") (pin "1") (pinfunction "1_1") (pintype "passive"))
      (node (ref "R56") (pin "2") (pinfunction "2_2") (pintype "passive"))
      (node (ref "R57") (pin "2") (pinfunction "2_2") (pintype "passive"))
    )
    (net (code "62") (name "Net-(IC8-OUT)") (class "Default")
      (node (ref "IC8") (pin "2") (pinfunction "OUT_2") (pintype "passive"))
      (node (ref "R26") (pin "2") (pinfunction "2_2") (pintype "passive"))
    )
    (net (code "63") (name "Net-(IC8-RS+)") (class "Default")
      (node (ref "C20") (pin "2") (pinfunction "2_2") (pintype "passive"))
      (node (ref "C21") (pin "2") (pinfunction "2_2") (pintype "passive"))
      (node (ref "C76") (pin "2") (pinfunction "2_2") (pintype "passive"))
      (node (ref "IC8") (pin "4") (pinfunction "RS+_4") (pintype "passive"))
      (node (ref "L4") (pin "2") (pinfunction "2_2") (pintype "passive"))
      (node (ref "R15") (pin "1") (pinfunction "1_1") (pintype "passive"))
      (node (ref "R91") (pin "2") (pinfunction "2_2") (pintype "passive"))
    )
    (net (code "64") (name "Net-(IC9-ISET)") (class "Default")
      (node (ref "IC9") (pin "3") (pinfunction "ISET_3") (pintype "passive"))
      (node (ref "R73") (pin "2") (pinfunction "2_2") (pintype "passive"))
    )
    (net (code "65") (name "Net-(IC12-OUT)") (class "Default")
      (node (ref "IC12") (pin "2") (pinfunction "OUT_2") (pintype "passive"))
      (node (ref "R27") (pin "2") (pinfunction "2_2") (pintype "passive"))
    )
    (net (code "66") (name "Net-(U1-BIAS)") (class "Default")
      (node (ref "C215") (pin "2") (pinfunction "2_2") (pintype "passive"))
      (node (ref "R8") (pin "1") (pinfunction "1_1") (pintype "passive"))
      (node (ref "U1") (pin "14") (pinfunction "BIAS_14") (pintype "power_in"))
    )
    (net (code "67") (name "Net-(U1-BST)") (class "Default")
      (node (ref "C6") (pin "1") (pinfunction "1_1") (pintype "passive"))
      (node (ref "U1") (pin "12") (pinfunction "BST_12") (pintype "passive"))
    )
    (net (code "68") (name "Net-(U1-EN{slash}UV)") (class "Default")
      (node (ref "R5") (pin "1") (pinfunction "1_1") (pintype "passive"))
      (node (ref "R89") (pin "1") (pinfunction "1_1") (pintype "passive"))
      (node (ref "U1") (pin "4") (pinfunction "EN/UV_4") (pintype "input"))
    )
    (net (code "69") (name "Net-(U1-FB)") (class "Default")
      (node (ref "C7") (pin "1") (pinfunction "1_1") (pintype "passive"))
      (node (ref "R2") (pin "1") (pinfunction "1_1") (pintype "passive"))
      (node (ref "R7") (pin "2") (pinfunction "2_2") (pintype "passive"))
      (node (ref "U1") (pin "16") (pinfunction "FB_16") (pintype "input"))
    )
    (net (code "70") (name "Net-(U1-INTVCC)") (class "Default")
      (node (ref "C216") (pin "2") (pinfunction "2_2") (pintype "passive"))
      (node (ref "U1") (pin "13") (pinfunction "INTVCC_13") (pintype "power_in"))
    )
    (net (code "71") (name "Net-(U1-RT)") (class "Default")
      (node (ref "R61") (pin "2") (pinfunction "2_2") (pintype "passive"))
      (node (ref "U1") (pin "3") (pinfunction "RT_3") (pintype "passive"))
    )
    (net (code "72") (name "Net-(U1-SYNC)") (class "Default")
      (node (ref "R4") (pin "2") (pinfunction "2_2") (pintype "passive"))
      (node (ref "U1") (pin "1") (pinfunction "SYNC_1") (pintype "input"))
    )
    (net (code "73") (name "Net-(U1-TR{slash}SS)") (class "Default")
      (node (ref "C214") (pin "2") (pinfunction "2_2") (pintype "passive"))
      (node (ref "U1") (pin "2") (pinfunction "TR/SS_2") (pintype "input"))
    )
    (net (code "74") (name "Net-(U6-BIAS)") (class "Default")
      (node (ref "C27") (pin "2") (pinfunction "2_2") (pintype "passive"))
      (node (ref "R19") (pin "1") (pinfunction "1_1") (pintype "passive"))
      (node (ref "U6") (pin "14") (pinfunction "BIAS_14") (pintype "power_in"))
    )
    (net (code "75") (name "Net-(U6-BST)") (class "Default")
      (node (ref "C19") (pin "1") (pinfunction "1_1") (pintype "passive"))
      (node (ref "U6") (pin "12") (pinfunction "BST_12") (pintype "passive"))
    )
    (net (code "76") (name "Net-(U6-FB)") (class "Default")
      (node (ref "C76") (pin "1") (pinfunction "1_1") (pintype "passive"))
      (node (ref "R18") (pin "2") (pinfunction "2_2") (pintype "passive"))
      (node (ref "R91") (pin "1") (pinfunction "1_1") (pintype "passive"))
      (node (ref "U6") (pin "16") (pinfunction "FB_16") (pintype "input"))
    )
    (net (code "77") (name "Net-(U6-INTVCC)") (class "Default")
      (node (ref "C28") (pin "2") (pinfunction "2_2") (pintype "passive"))
      (node (ref "U6") (pin "13") (pinfunction "INTVCC_13") (pintype "power_in"))
    )
    (net (code "78") (name "Net-(U6-RT)") (class "Default")
      (node (ref "R21") (pin "2") (pinfunction "2_2") (pintype "passive"))
      (node (ref "U6") (pin "3") (pinfunction "RT_3") (pintype "passive"))
    )
    (net (code "79") (name "Net-(U6-SYNC)") (class "Default")
      (node (ref "R17") (pin "2") (pinfunction "2_2") (pintype "passive"))
      (node (ref "U6") (pin "1") (pinfunction "SYNC_1") (pintype "input"))
    )
    (net (code "80") (name "Net-(U6-TR{slash}SS)") (class "Default")
      (node (ref "C24") (pin "2") (pinfunction "2_2") (pintype "passive"))
      (node (ref "U6") (pin "2") (pinfunction "TR/SS_2") (pintype "input"))
    )
    (net (code "81") (name "Net-(U7-BST)") (class "Default")
      (node (ref "C30") (pin "1") (pinfunction "1_1") (pintype "passive"))
      (node (ref "U7") (pin "12") (pinfunction "BST_12") (pintype "passive"))
    )
    (net (code "82") (name "Net-(U7-FB)") (class "Default")
      (node (ref "C80") (pin "1") (pinfunction "1_1") (pintype "passive"))
      (node (ref "R28") (pin "1") (pinfunction "1_1") (pintype "passive"))
      (node (ref "R30") (pin "2") (pinfunction "2_2") (pintype "passive"))
      (node (ref "U7") (pin "16") (pinfunction "FB_16") (pintype "input"))
    )
    (net (code "83") (name "Net-(U7-INTVCC)") (class "Default")
      (node (ref "C32") (pin "2") (pinfunction "2_2") (pintype "passive"))
      (node (ref "U7") (pin "13") (pinfunction "INTVCC_13") (pintype "power_in"))
    )
    (net (code "84") (name "Net-(U7-RT)") (class "Default")
      (node (ref "R29") (pin "2") (pinfunction "2_2") (pintype "passive"))
      (node (ref "U7") (pin "3") (pinfunction "RT_3") (pintype "passive"))
    )
    (net (code "85") (name "Net-(U7-SYNC)") (class "Default")
      (node (ref "R25") (pin "2") (pinfunction "2_2") (pintype "passive"))
      (node (ref "U7") (pin "1") (pinfunction "SYNC_1") (pintype "input"))
    )
    (net (code "86") (name "Net-(U7-TR{slash}SS)") (class "Default")
      (node (ref "C31") (pin "2") (pinfunction "2_2") (pintype "passive"))
      (node (ref "U7") (pin "2") (pinfunction "TR/SS_2") (pintype "input"))
    )
    (net (code "87") (name "P3V3_buck") (class "Default")
      (node (ref "C78") (pin "2") (pinfunction "2_2") (pintype "passive"))
      (node (ref "C79") (pin "2") (pinfunction "2_2") (pintype "passive"))
      (node (ref "C80") (pin "2") (pinfunction "2_2") (pintype "passive"))
      (node (ref "IC12") (pin "4") (pinfunction "RS+_4") (pintype "passive"))
      (node (ref "L6") (pin "2") (pinfunction "2_2") (pintype "passive"))
      (node (ref "R19") (pin "2") (pinfunction "2_2") (pintype "passive"))
      (node (ref "R22") (pin "1") (pinfunction "1_1") (pintype "passive"))
      (node (ref "R28") (pin "2") (pinfunction "2_2") (pintype "passive"))
      (node (ref "R8") (pin "2") (pinfunction "2_2") (pintype "passive"))
      (node (ref "U7") (pin "14") (pinfunction "BIAS_14") (pintype "power_in"))
    )
    (net (code "88") (name "P12V0_IN") (class "Default")
      (node (ref "C74") (pin "2") (pinfunction "2_2") (pintype "passive"))
      (node (ref "IC4") (pin "3") (pinfunction "VCC_3") (pintype "passive"))
      (node (ref "IC6") (pin "1") (pinfunction "VIN_1") (pintype "passive"))
      (node (ref "IC9") (pin "1") (pinfunction "VIN_1") (pintype "passive"))
    )
    (net (code "89") (name "unconnected-(IC6-NC-Pad6)") (class "Default")
      (node (ref "IC6") (pin "6") (pinfunction "NC_6") (pintype "passive+no_connect"))
    )
    (net (code "90") (name "unconnected-(IC9-NC-Pad6)") (class "Default")
      (node (ref "IC9") (pin "6") (pinfunction "NC_6") (pintype "passive+no_connect"))
    )
  )
)
